# RaspComputeModule_4_IO.net
KiCad netlist of a schematic drawn in Altium Designer
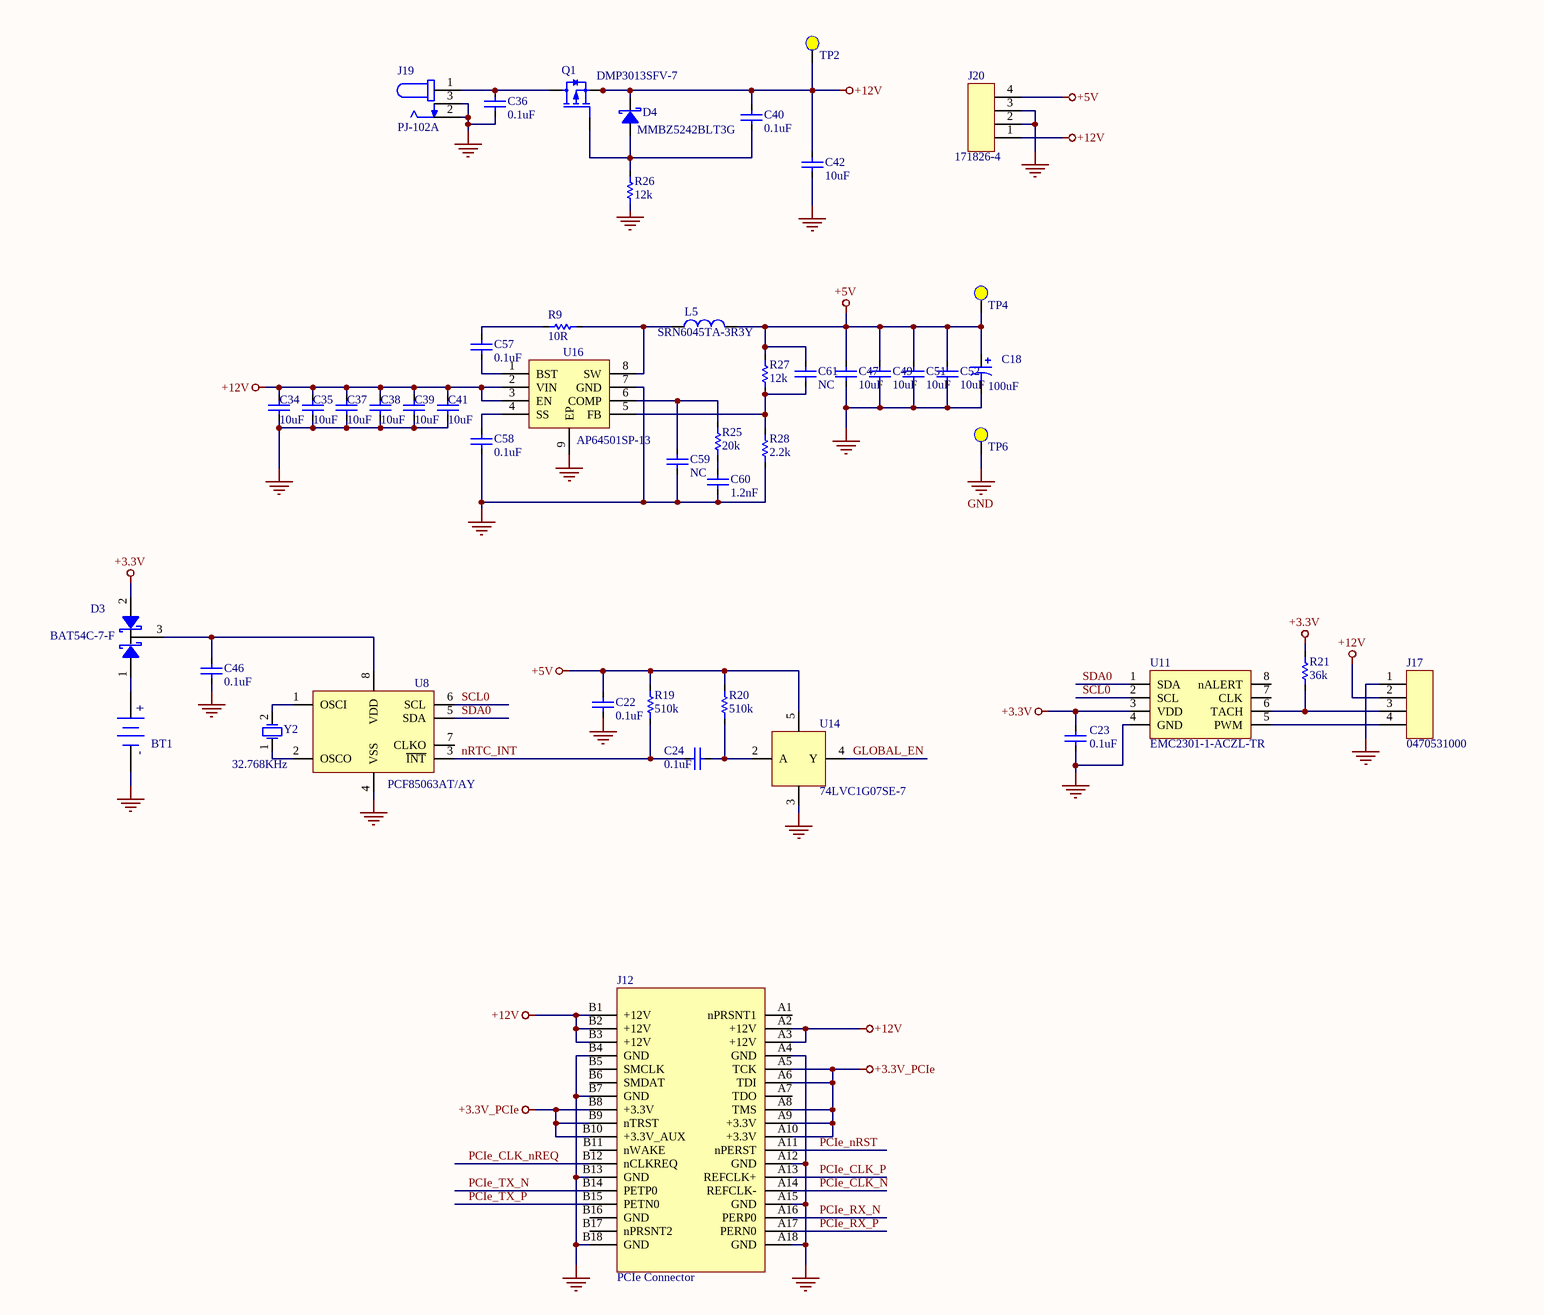
[diagram p0: RaspComputeModule_4_IO.SchDoc, top left]
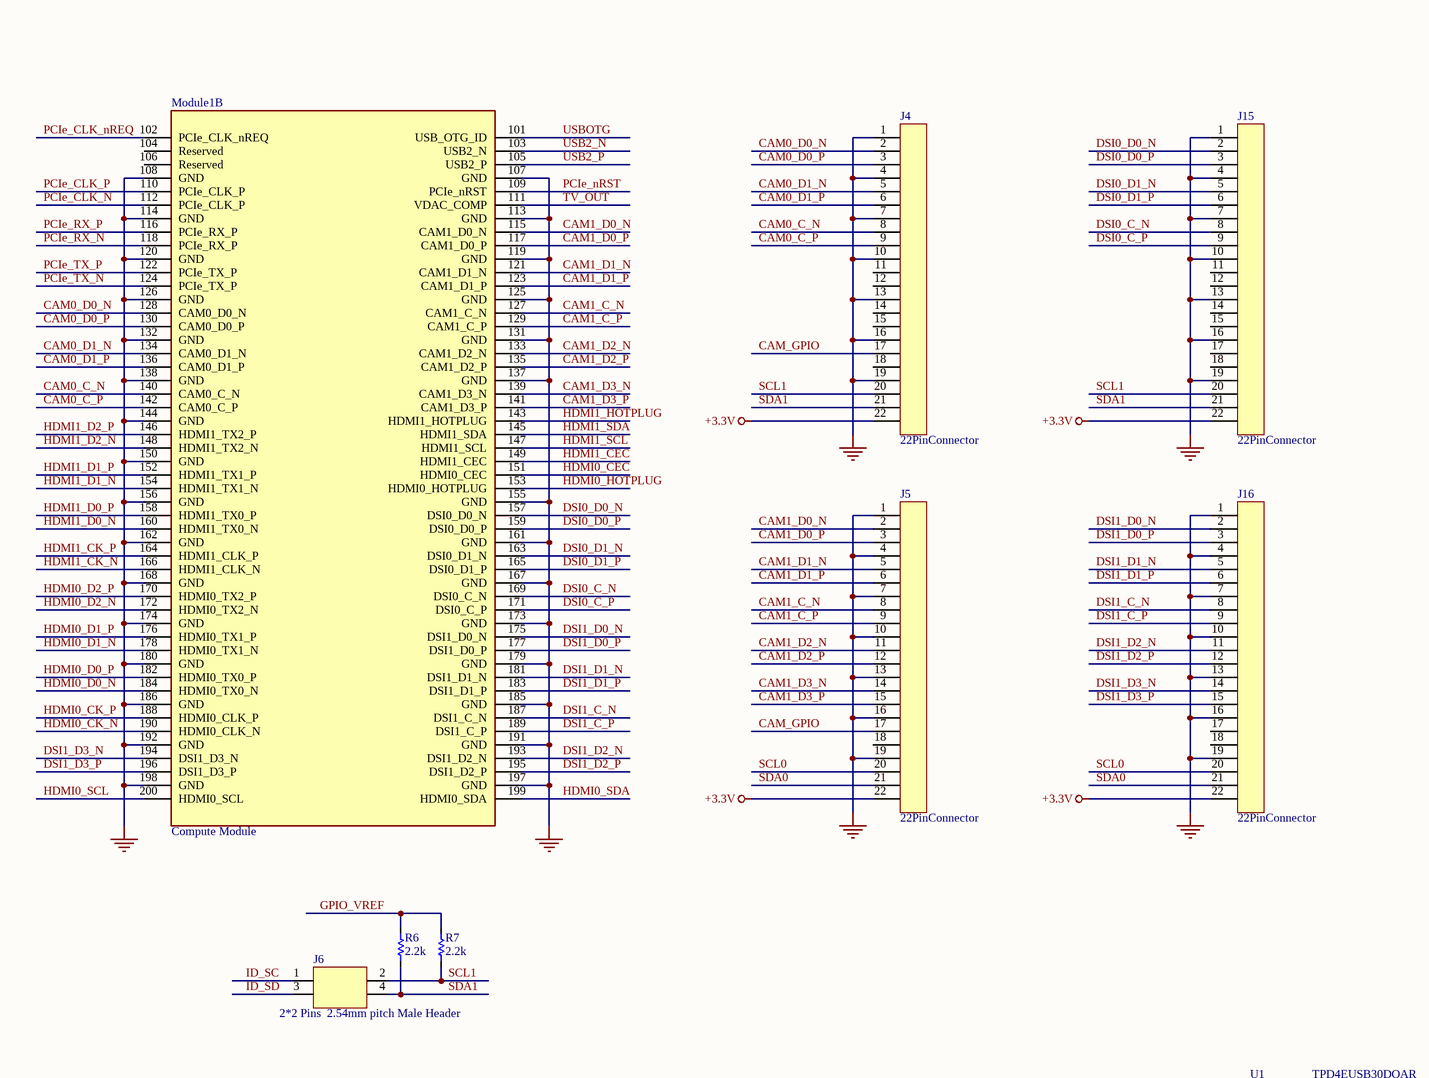
[diagram p1: RaspComputeModule_4_IO.SchDoc, top right]
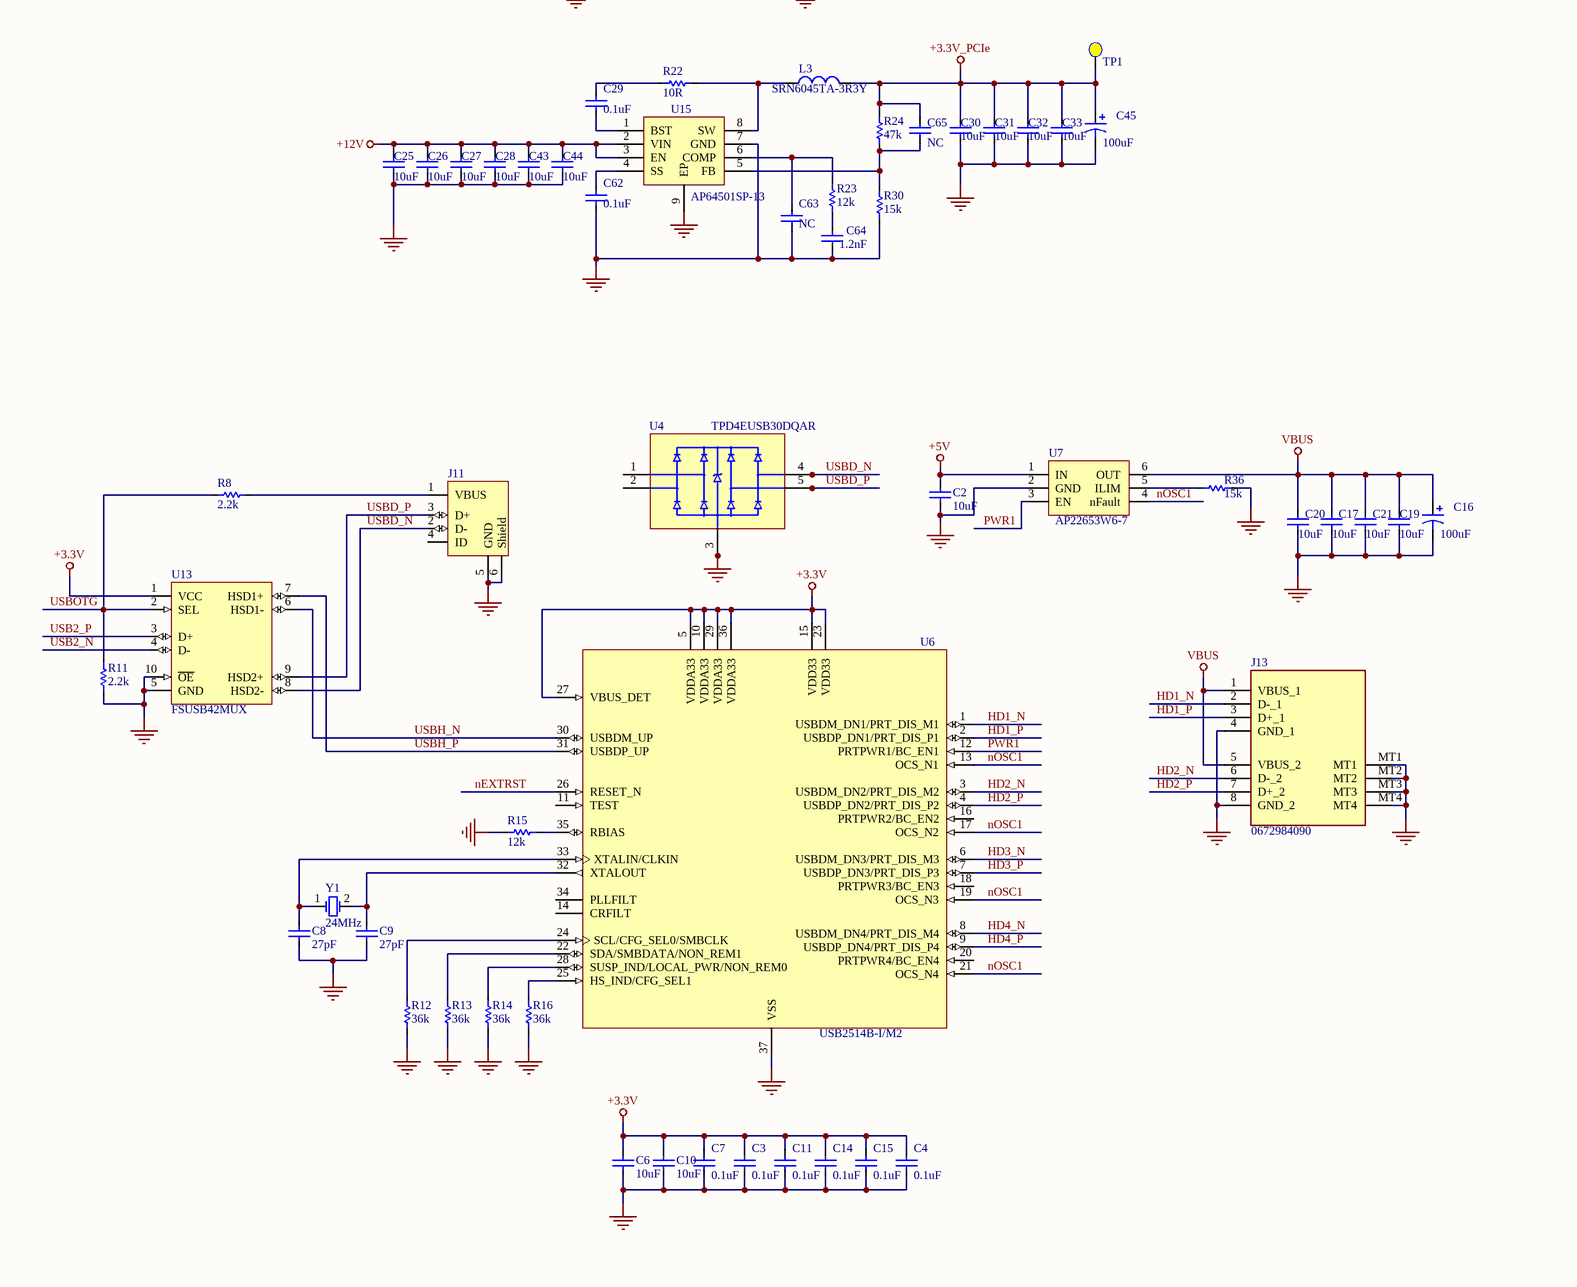
[diagram p2: RaspComputeModule_4_IO.SchDoc, bottom left]
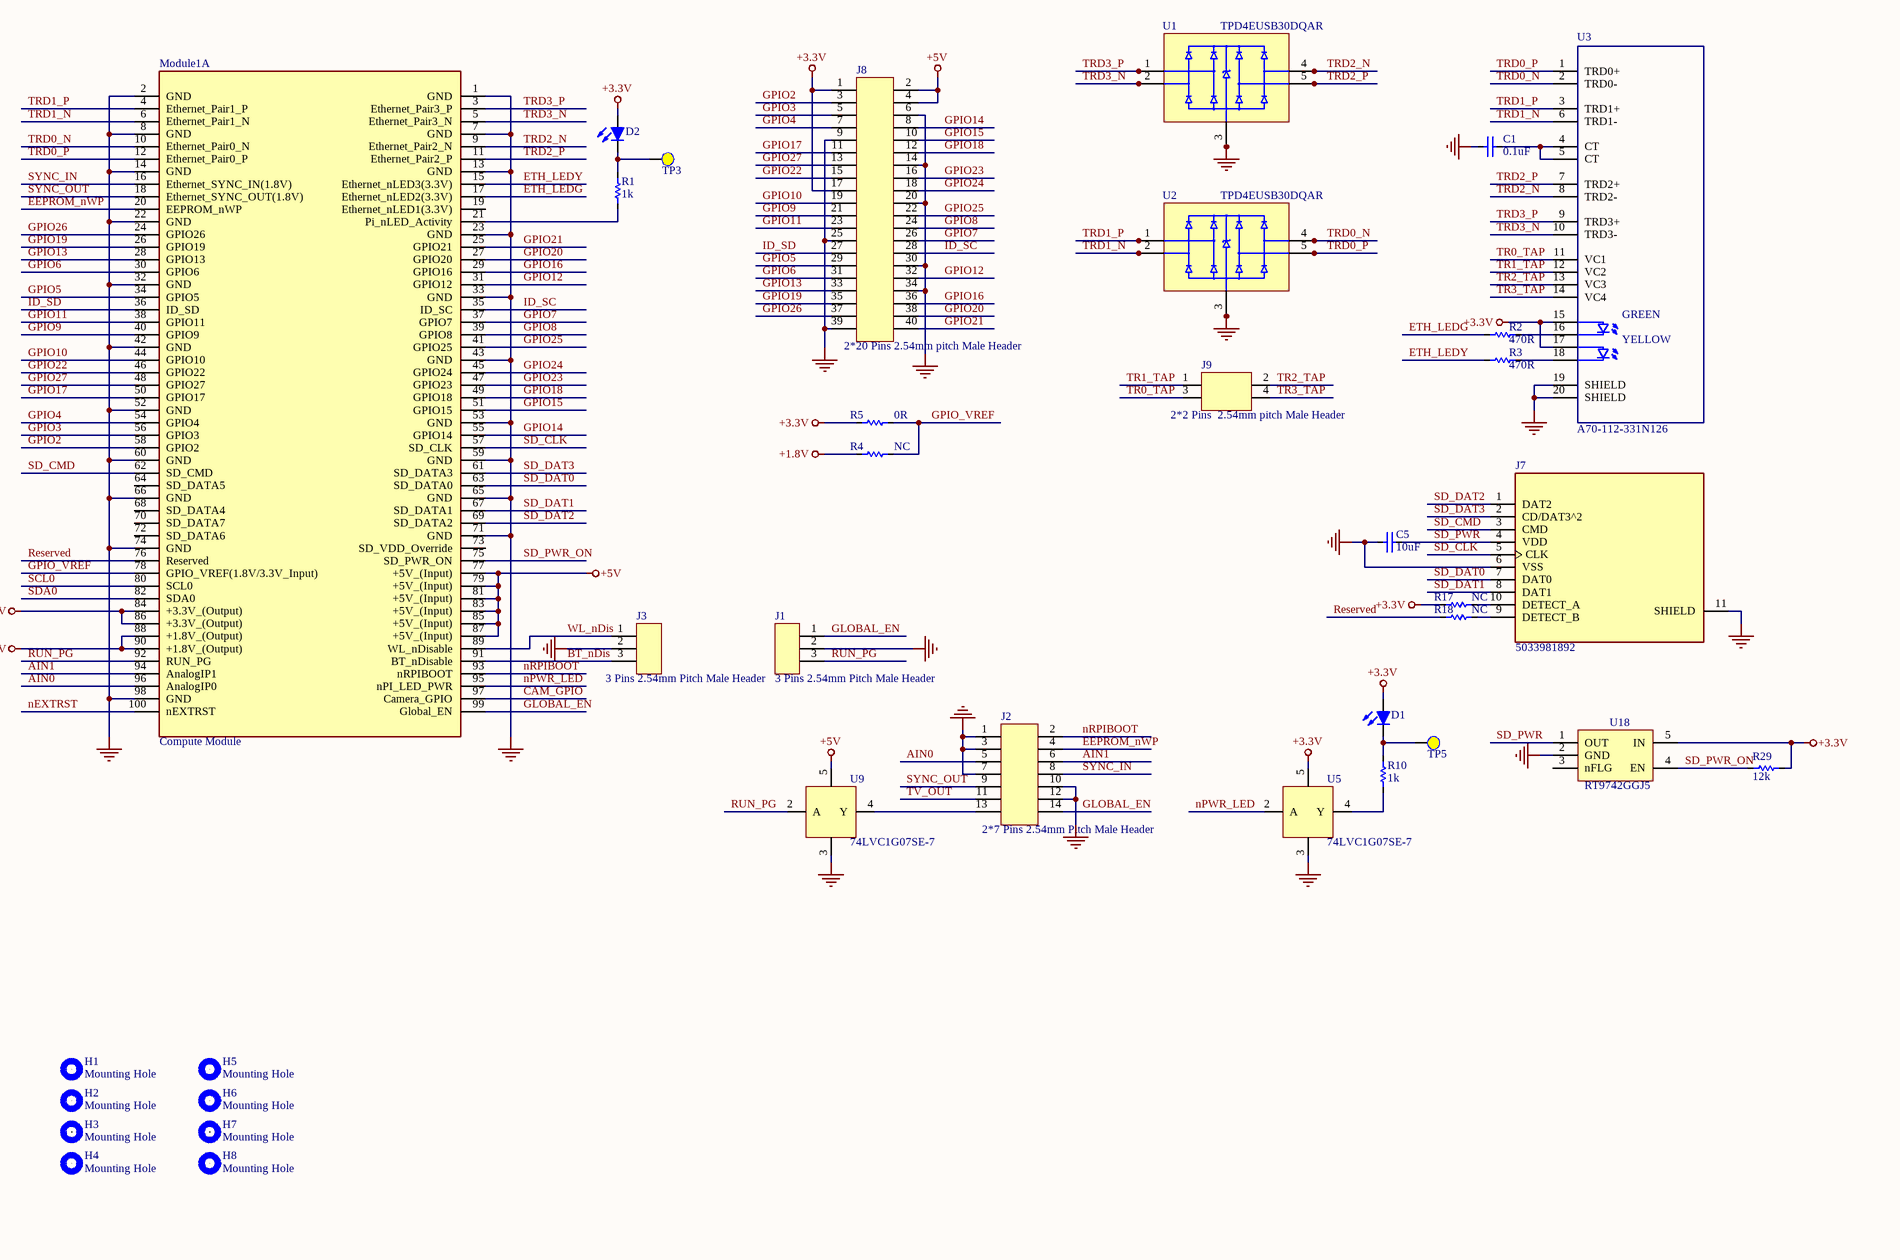
[diagram p3: RaspComputeModule_4_IO.SchDoc, bottom right]

(export (version "E")
  (design (tool "Eeschema 10.0.6"))
  (components
    (comp (ref "BT1")
      (value "3034")
      (footprint "BatteryHolder_Keystone_3034_1x20mm")
      (description "BATTERY RETAINER COIN 20MM SMD")
      (fields (field (name "MANUFACTURER") "Keystone Electronics"))
      (libsource (lib "schematic_library") (part "BATTERY_18650"))
    )
    (comp (ref "C1")
      (value "0.1uF")
      (footprint "C_0402_1005Metric")
      (description "0.1µF ±10% 50V")
      (fields
        (field (name "MANUFACTURER") "Yageo")
        (field (name "MANUFACTURER PART NUMBER") "CC0402KRX5R9BB104")
      )
      (libsource (lib "Miscellaneous Devices") (part "Cap"))
    )
    (comp (ref "C2")
      (value "10uF")
      (footprint "C_0805_2012Metric")
      (description "10µF ±10% 35V")
      (fields
        (field (name "MANUFACTURER") "Murata")
        (field (name "MANUFACTURER PART NUMBER") "GRM21BR6YA106KE43L")
      )
      (libsource (lib "Miscellaneous Devices") (part "Cap"))
    )
    (comp (ref "C3")
      (value "0.1uF")
      (footprint "C_0402_1005Metric")
      (description "0.1µF ±10% 50V")
      (fields
        (field (name "MANUFACTURER") "Yageo")
        (field (name "MANUFACTURER PART NUMBER") "CC0402KRX5R9BB104")
      )
      (libsource (lib "Miscellaneous Devices") (part "Cap"))
    )
    (comp (ref "C4")
      (value "0.1uF")
      (footprint "C_0402_1005Metric")
      (description "0.1µF ±10% 50V")
      (fields
        (field (name "MANUFACTURER") "Yageo")
        (field (name "MANUFACTURER PART NUMBER") "CC0402KRX5R9BB104")
      )
      (libsource (lib "Miscellaneous Devices") (part "Cap"))
    )
    (comp (ref "C5")
      (value "10uF")
      (footprint "C_0805_2012Metric")
      (description "10µF ±10% 35V")
      (fields
        (field (name "MANUFACTURER") "Murata")
        (field (name "MANUFACTURER PART NUMBER") "GRM21BR6YA106KE43L")
      )
      (libsource (lib "Miscellaneous Devices") (part "Cap"))
    )
    (comp (ref "C6")
      (value "10uF")
      (footprint "C_0805_2012Metric")
      (description "10µF ±10% 35V")
      (fields
        (field (name "MANUFACTURER") "Murata")
        (field (name "MANUFACTURER PART NUMBER") "GRM21BR6YA106KE43L")
      )
      (libsource (lib "Miscellaneous Devices") (part "Cap"))
    )
    (comp (ref "C7")
      (value "0.1uF")
      (footprint "C_0402_1005Metric")
      (description "0.1µF ±10% 50V")
      (fields
        (field (name "MANUFACTURER") "Yageo")
        (field (name "MANUFACTURER PART NUMBER") "CC0402KRX5R9BB104")
      )
      (libsource (lib "Miscellaneous Devices") (part "Cap"))
    )
    (comp (ref "C8")
      (value "27pF")
      (footprint "C_0402_1005Metric")
      (description "27pF ±1% 50V")
      (fields
        (field (name "MANUFACTURER") "Yageo")
        (field (name "MANUFACTURER PART NUMBER") "CC0402FRNPO9BN270")
      )
      (libsource (lib "Miscellaneous Devices") (part "Cap"))
    )
    (comp (ref "C9")
      (value "27pF")
      (footprint "C_0402_1005Metric")
      (description "27pF ±1% 50V")
      (fields
        (field (name "MANUFACTURER") "Yageo")
        (field (name "MANUFACTURER PART NUMBER") "CC0402FRNPO9BN270")
      )
      (libsource (lib "Miscellaneous Devices") (part "Cap"))
    )
    (comp (ref "C10")
      (value "10uF")
      (footprint "C_0805_2012Metric")
      (description "10µF ±10% 35V")
      (fields
        (field (name "MANUFACTURER") "Murata")
        (field (name "MANUFACTURER PART NUMBER") "GRM21BR6YA106KE43L")
      )
      (libsource (lib "Miscellaneous Devices") (part "Cap"))
    )
    (comp (ref "C11")
      (value "0.1uF")
      (footprint "C_0402_1005Metric")
      (description "0.1µF ±10% 50V")
      (fields
        (field (name "MANUFACTURER") "Yageo")
        (field (name "MANUFACTURER PART NUMBER") "CC0402KRX5R9BB104")
      )
      (libsource (lib "Miscellaneous Devices") (part "Cap"))
    )
    (comp (ref "C14")
      (value "0.1uF")
      (footprint "C_0402_1005Metric")
      (description "0.1µF ±10% 50V")
      (fields
        (field (name "MANUFACTURER") "Yageo")
        (field (name "MANUFACTURER PART NUMBER") "CC0402KRX5R9BB104")
      )
      (libsource (lib "Miscellaneous Devices") (part "Cap"))
    )
    (comp (ref "C15")
      (value "0.1uF")
      (footprint "C_0402_1005Metric")
      (description "0.1µF ±10% 50V")
      (fields
        (field (name "MANUFACTURER") "Yageo")
        (field (name "MANUFACTURER PART NUMBER") "CC0402KRX5R9BB104")
      )
      (libsource (lib "Miscellaneous Devices") (part "Cap"))
    )
    (comp (ref "C16")
      (value "100uF")
      (footprint "CP_EIA-7343-31_Kemet-D")
      (description "CAP TANT 100UF 20% 10V 2917")
      (fields
        (field (name "MANUFACTURER PART NUMBER") "TAJD107M010RNJ")
        (field (name "MANUFACTURER") "AVX Corporation")
      )
      (libsource (lib "Miscellaneous Devices") (part "Cap Pol1"))
    )
    (comp (ref "C17")
      (value "10uF")
      (footprint "C_0805_2012Metric")
      (description "10µF ±10% 35V")
      (fields
        (field (name "MANUFACTURER") "Murata")
        (field (name "MANUFACTURER PART NUMBER") "GRM21BR6YA106KE43L")
      )
      (libsource (lib "Miscellaneous Devices") (part "Cap"))
    )
    (comp (ref "C18")
      (value "100uF")
      (footprint "CP_EIA-7343-31_Kemet-D")
      (description "CAP TANT 100UF 20% 10V 2917")
      (fields
        (field (name "MANUFACTURER PART NUMBER") "TAJD107M010RNJ")
        (field (name "MANUFACTURER") "AVX Corporation")
      )
      (libsource (lib "Miscellaneous Devices") (part "Cap Pol1"))
    )
    (comp (ref "C19")
      (value "10uF")
      (footprint "C_0805_2012Metric")
      (description "10µF ±10% 35V")
      (fields
        (field (name "MANUFACTURER") "Murata")
        (field (name "MANUFACTURER PART NUMBER") "GRM21BR6YA106KE43L")
      )
      (libsource (lib "Miscellaneous Devices") (part "Cap"))
    )
    (comp (ref "C20")
      (value "10uF")
      (footprint "C_0805_2012Metric")
      (description "10µF ±10% 35V")
      (fields
        (field (name "MANUFACTURER") "Murata")
        (field (name "MANUFACTURER PART NUMBER") "GRM21BR6YA106KE43L")
      )
      (libsource (lib "Miscellaneous Devices") (part "Cap"))
    )
    (comp (ref "C21")
      (value "10uF")
      (footprint "C_0805_2012Metric")
      (description "10µF ±10% 35V")
      (fields
        (field (name "MANUFACTURER") "Murata")
        (field (name "MANUFACTURER PART NUMBER") "GRM21BR6YA106KE43L")
      )
      (libsource (lib "Miscellaneous Devices") (part "Cap"))
    )
    (comp (ref "C22")
      (value "0.1uF")
      (footprint "C_0402_1005Metric")
      (description "0.1µF ±10% 50V")
      (fields
        (field (name "MANUFACTURER") "Yageo")
        (field (name "MANUFACTURER PART NUMBER") "CC0402KRX5R9BB104")
      )
      (libsource (lib "Miscellaneous Devices") (part "Cap"))
    )
    (comp (ref "C23")
      (value "0.1uF")
      (footprint "C_0402_1005Metric")
      (description "0.1µF ±10% 50V")
      (fields
        (field (name "MANUFACTURER") "Yageo")
        (field (name "MANUFACTURER PART NUMBER") "CC0402KRX5R9BB104")
      )
      (libsource (lib "Miscellaneous Devices") (part "Cap"))
    )
    (comp (ref "C24")
      (value "0.1uF")
      (footprint "C_0402_1005Metric")
      (description "0.1µF ±10% 50V")
      (fields
        (field (name "MANUFACTURER") "Yageo")
        (field (name "MANUFACTURER PART NUMBER") "CC0402KRX5R9BB104")
      )
      (libsource (lib "Miscellaneous Devices") (part "Cap"))
    )
    (comp (ref "C25")
      (value "10uF")
      (footprint "C_0805_2012Metric")
      (description "10µF ±10% 35V")
      (fields
        (field (name "MANUFACTURER") "Murata")
        (field (name "MANUFACTURER PART NUMBER") "GRM21BR6YA106KE43L")
      )
      (libsource (lib "Miscellaneous Devices") (part "Cap"))
    )
    (comp (ref "C26")
      (value "10uF")
      (footprint "C_0805_2012Metric")
      (description "10µF ±10% 35V")
      (fields
        (field (name "MANUFACTURER") "Murata")
        (field (name "MANUFACTURER PART NUMBER") "GRM21BR6YA106KE43L")
      )
      (libsource (lib "Miscellaneous Devices") (part "Cap"))
    )
    (comp (ref "C27")
      (value "10uF")
      (footprint "C_0805_2012Metric")
      (description "10µF ±10% 35V")
      (fields
        (field (name "MANUFACTURER") "Murata")
        (field (name "MANUFACTURER PART NUMBER") "GRM21BR6YA106KE43L")
      )
      (libsource (lib "Miscellaneous Devices") (part "Cap"))
    )
    (comp (ref "C28")
      (value "10uF")
      (footprint "C_0805_2012Metric")
      (description "10µF ±10% 35V")
      (fields
        (field (name "MANUFACTURER") "Murata")
        (field (name "MANUFACTURER PART NUMBER") "GRM21BR6YA106KE43L")
      )
      (libsource (lib "Miscellaneous Devices") (part "Cap"))
    )
    (comp (ref "C29")
      (value "0.1uF")
      (footprint "C_0402_1005Metric")
      (description "0.1µF ±10% 50V")
      (fields
        (field (name "MANUFACTURER") "Yageo")
        (field (name "MANUFACTURER PART NUMBER") "CC0402KRX5R9BB104")
      )
      (libsource (lib "Miscellaneous Devices") (part "Cap"))
    )
    (comp (ref "C30")
      (value "10uF")
      (footprint "C_0805_2012Metric")
      (description "10µF ±10% 35V")
      (fields
        (field (name "MANUFACTURER") "Murata")
        (field (name "MANUFACTURER PART NUMBER") "GRM21BR6YA106KE43L")
      )
      (libsource (lib "Miscellaneous Devices") (part "Cap"))
    )
    (comp (ref "C31")
      (value "10uF")
      (footprint "C_0805_2012Metric")
      (description "10µF ±10% 35V")
      (fields
        (field (name "MANUFACTURER") "Murata")
        (field (name "MANUFACTURER PART NUMBER") "GRM21BR6YA106KE43L")
      )
      (libsource (lib "Miscellaneous Devices") (part "Cap"))
    )
    (comp (ref "C32")
      (value "10uF")
      (footprint "C_0805_2012Metric")
      (description "10µF ±10% 35V")
      (fields
        (field (name "MANUFACTURER") "Murata")
        (field (name "MANUFACTURER PART NUMBER") "GRM21BR6YA106KE43L")
      )
      (libsource (lib "Miscellaneous Devices") (part "Cap"))
    )
    (comp (ref "C33")
      (value "10uF")
      (footprint "C_0805_2012Metric")
      (description "10µF ±10% 35V")
      (fields
        (field (name "MANUFACTURER") "Murata")
        (field (name "MANUFACTURER PART NUMBER") "GRM21BR6YA106KE43L")
      )
      (libsource (lib "Miscellaneous Devices") (part "Cap"))
    )
    (comp (ref "C34")
      (value "10uF")
      (footprint "C_0805_2012Metric")
      (description "10µF ±10% 35V")
      (fields
        (field (name "MANUFACTURER") "Murata")
        (field (name "MANUFACTURER PART NUMBER") "GRM21BR6YA106KE43L")
      )
      (libsource (lib "Miscellaneous Devices") (part "Cap"))
    )
    (comp (ref "C35")
      (value "10uF")
      (footprint "C_0805_2012Metric")
      (description "10µF ±10% 35V")
      (fields
        (field (name "MANUFACTURER") "Murata")
        (field (name "MANUFACTURER PART NUMBER") "GRM21BR6YA106KE43L")
      )
      (libsource (lib "Miscellaneous Devices") (part "Cap"))
    )
    (comp (ref "C36")
      (value "0.1uF")
      (footprint "C_0402_1005Metric")
      (description "0.1µF ±10% 50V")
      (fields
        (field (name "MANUFACTURER") "Yageo")
        (field (name "MANUFACTURER PART NUMBER") "CC0402KRX5R9BB104")
      )
      (libsource (lib "Miscellaneous Devices") (part "Cap"))
    )
    (comp (ref "C37")
      (value "10uF")
      (footprint "C_0805_2012Metric")
      (description "10µF ±10% 35V")
      (fields
        (field (name "MANUFACTURER") "Murata")
        (field (name "MANUFACTURER PART NUMBER") "GRM21BR6YA106KE43L")
      )
      (libsource (lib "Miscellaneous Devices") (part "Cap"))
    )
    (comp (ref "C38")
      (value "10uF")
      (footprint "C_0805_2012Metric")
      (description "10µF ±10% 35V")
      (fields
        (field (name "MANUFACTURER") "Murata")
        (field (name "MANUFACTURER PART NUMBER") "GRM21BR6YA106KE43L")
      )
      (libsource (lib "Miscellaneous Devices") (part "Cap"))
    )
    (comp (ref "C39")
      (value "10uF")
      (footprint "C_0805_2012Metric")
      (description "10µF ±10% 35V")
      (fields
        (field (name "MANUFACTURER") "Murata")
        (field (name "MANUFACTURER PART NUMBER") "GRM21BR6YA106KE43L")
      )
      (libsource (lib "Miscellaneous Devices") (part "Cap"))
    )
    (comp (ref "C40")
      (value "0.1uF")
      (footprint "C_0402_1005Metric")
      (description "0.1µF ±10% 50V")
      (fields
        (field (name "MANUFACTURER") "Yageo")
        (field (name "MANUFACTURER PART NUMBER") "CC0402KRX5R9BB104")
      )
      (libsource (lib "Miscellaneous Devices") (part "Cap"))
    )
    (comp (ref "C41")
      (value "10uF")
      (footprint "C_0805_2012Metric")
      (description "10µF ±10% 35V")
      (fields
        (field (name "MANUFACTURER") "Murata")
        (field (name "MANUFACTURER PART NUMBER") "GRM21BR6YA106KE43L")
      )
      (libsource (lib "Miscellaneous Devices") (part "Cap"))
    )
    (comp (ref "C42")
      (value "10uF")
      (footprint "C_0805_2012Metric")
      (description "10µF ±10% 35V")
      (fields
        (field (name "MANUFACTURER") "Murata")
        (field (name "MANUFACTURER PART NUMBER") "GRM21BR6YA106KE43L")
      )
      (libsource (lib "Miscellaneous Devices") (part "Cap"))
    )
    (comp (ref "C43")
      (value "10uF")
      (footprint "C_0805_2012Metric")
      (description "10µF ±10% 35V")
      (fields
        (field (name "MANUFACTURER") "Murata")
        (field (name "MANUFACTURER PART NUMBER") "GRM21BR6YA106KE43L")
      )
      (libsource (lib "Miscellaneous Devices") (part "Cap"))
    )
    (comp (ref "C44")
      (value "10uF")
      (footprint "C_0805_2012Metric")
      (description "10µF ±10% 35V")
      (fields
        (field (name "MANUFACTURER") "Murata")
        (field (name "MANUFACTURER PART NUMBER") "GRM21BR6YA106KE43L")
      )
      (libsource (lib "Miscellaneous Devices") (part "Cap"))
    )
    (comp (ref "C45")
      (value "100uF")
      (footprint "CP_EIA-7343-31_Kemet-D")
      (description "CAP TANT 100UF 20% 10V 2917")
      (fields
        (field (name "MANUFACTURER PART NUMBER") "TAJD107M010RNJ")
        (field (name "MANUFACTURER") "AVX Corporation")
      )
      (libsource (lib "Miscellaneous Devices") (part "Cap Pol1"))
    )
    (comp (ref "C46")
      (value "0.1uF")
      (footprint "C_0402_1005Metric")
      (description "0.1µF ±10% 50V")
      (fields
        (field (name "MANUFACTURER") "Yageo")
        (field (name "MANUFACTURER PART NUMBER") "CC0402KRX5R9BB104")
      )
      (libsource (lib "Miscellaneous Devices") (part "Cap"))
    )
    (comp (ref "C47")
      (value "10uF")
      (footprint "C_0805_2012Metric")
      (description "10µF ±10% 35V")
      (fields
        (field (name "MANUFACTURER") "Murata")
        (field (name "MANUFACTURER PART NUMBER") "GRM21BR6YA106KE43L")
      )
      (libsource (lib "Miscellaneous Devices") (part "Cap"))
    )
    (comp (ref "C49")
      (value "10uF")
      (footprint "C_0805_2012Metric")
      (description "10µF ±10% 35V")
      (fields
        (field (name "MANUFACTURER") "Murata")
        (field (name "MANUFACTURER PART NUMBER") "GRM21BR6YA106KE43L")
      )
      (libsource (lib "Miscellaneous Devices") (part "Cap"))
    )
    (comp (ref "C51")
      (value "10uF")
      (footprint "C_0805_2012Metric")
      (description "10µF ±10% 35V")
      (fields
        (field (name "MANUFACTURER") "Murata")
        (field (name "MANUFACTURER PART NUMBER") "GRM21BR6YA106KE43L")
      )
      (libsource (lib "Miscellaneous Devices") (part "Cap"))
    )
    (comp (ref "C52")
      (value "10uF")
      (footprint "C_0805_2012Metric")
      (description "10µF ±10% 35V")
      (fields
        (field (name "MANUFACTURER") "Murata")
        (field (name "MANUFACTURER PART NUMBER") "GRM21BR6YA106KE43L")
      )
      (libsource (lib "Miscellaneous Devices") (part "Cap"))
    )
    (comp (ref "C57")
      (value "0.1uF")
      (footprint "C_0402_1005Metric")
      (description "0.1µF ±10% 50V")
      (fields
        (field (name "MANUFACTURER") "Yageo")
        (field (name "MANUFACTURER PART NUMBER") "CC0402KRX5R9BB104")
      )
      (libsource (lib "Miscellaneous Devices") (part "Cap"))
    )
    (comp (ref "C58")
      (value "0.1uF")
      (footprint "C_0402_1005Metric")
      (description "0.1µF ±10% 50V")
      (fields
        (field (name "MANUFACTURER") "Yageo")
        (field (name "MANUFACTURER PART NUMBER") "CC0402KRX5R9BB104")
      )
      (libsource (lib "Miscellaneous Devices") (part "Cap"))
    )
    (comp (ref "C59")
      (value "NC")
      (footprint "C_0402_1005Metric")
      (libsource (lib "Miscellaneous Devices") (part "Cap"))
    )
    (comp (ref "C60")
      (value "1.2nF")
      (footprint "C_0402_1005Metric")
      (description "1200pF ±10% 50V")
      (fields
        (field (name "MANUFACTURER") "Murata")
        (field (name "MANUFACTURER PART NUMBER") "GRM155R71H122KA01J")
      )
      (libsource (lib "Miscellaneous Devices") (part "Cap"))
    )
    (comp (ref "C61")
      (value "NC")
      (footprint "C_0402_1005Metric")
      (libsource (lib "Miscellaneous Devices") (part "Cap"))
    )
    (comp (ref "C62")
      (value "0.1uF")
      (footprint "C_0402_1005Metric")
      (description "0.1µF ±10% 50V")
      (fields
        (field (name "MANUFACTURER") "Yageo")
        (field (name "MANUFACTURER PART NUMBER") "CC0402KRX5R9BB104")
      )
      (libsource (lib "Miscellaneous Devices") (part "Cap"))
    )
    (comp (ref "C63")
      (value "NC")
      (footprint "C_0402_1005Metric")
      (libsource (lib "Miscellaneous Devices") (part "Cap"))
    )
    (comp (ref "C64")
      (value "1.2nF")
      (footprint "C_0402_1005Metric")
      (description "1200pF ±10% 50V")
      (fields
        (field (name "MANUFACTURER") "Murata")
        (field (name "MANUFACTURER PART NUMBER") "GRM155R71H122KA01J")
      )
      (libsource (lib "Miscellaneous Devices") (part "Cap"))
    )
    (comp (ref "C65")
      (value "NC")
      (footprint "C_0402_1005Metric")
      (libsource (lib "Miscellaneous Devices") (part "Cap"))
    )
    (comp (ref "D1")
      (value "SML-D12U1WT86")
      (footprint "LED_0603_1608Metric")
      (description "LED RED DIFFUSED 0603 SMD")
      (fields (field (name "MANUFACTURER") "Rohm Semiconductor"))
      (libsource (lib "WirelessCharger") (part "LED1"))
    )
    (comp (ref "D2")
      (value "SML-D12U1WT86")
      (footprint "LED_0603_1608Metric")
      (description "LED RED DIFFUSED 0603 SMD")
      (fields (field (name "MANUFACTURER") "Rohm Semiconductor"))
      (libsource (lib "WirelessCharger") (part "LED1"))
    )
    (comp (ref "D3")
      (value "BAT54C-7-F")
      (footprint "SOT-23")
      (description "DIODE ARRAY SCHOTTKY 30V SOT323")
      (fields
        (field (name "MANUFACTURER") "ON Semiconductor")
        (field (name "MANUFACTURER PART NUMBER") "BAT54CWT1G")
      )
      (libsource (lib "WirelessCharger") (part "BAT54C-7-F"))
    )
    (comp (ref "D4")
      (value "MMBZ5242BLT3G")
      (footprint "D_SOT-23_ANK")
      (description "DIODE ZENER 12V 225MW SOT23-3")
      (fields (field (name "MANUFACTURER") "ON Semiconductor"))
      (libsource (lib "WirelessCharger") (part "Diode 10TQ035"))
    )
    (comp (ref "H1")
      (value "Mounting Hole")
      (footprint "MountingHole_2.7mm_M2.5")
      (libsource (lib "WirelessCharger") (part "Mounting Hole"))
    )
    (comp (ref "H2")
      (value "Mounting Hole")
      (footprint "MountingHole_2.7mm_M2.5")
      (libsource (lib "WirelessCharger") (part "Mounting Hole"))
    )
    (comp (ref "H3")
      (value "Mounting Hole")
      (footprint "MountingHole_2.7mm_M2.5")
      (libsource (lib "WirelessCharger") (part "Mounting Hole"))
    )
    (comp (ref "H4")
      (value "Mounting Hole")
      (footprint "MountingHole_2.7mm_M2.5")
      (libsource (lib "WirelessCharger") (part "Mounting Hole"))
    )
    (comp (ref "H5")
      (value "Mounting Hole")
      (footprint "MountingHole_2.7mm_M2.5")
      (libsource (lib "WirelessCharger") (part "Mounting Hole"))
    )
    (comp (ref "H6")
      (value "Mounting Hole")
      (footprint "MountingHole_2.7mm_M2.5")
      (libsource (lib "WirelessCharger") (part "Mounting Hole"))
    )
    (comp (ref "H7")
      (value "Mounting Hole")
      (footprint "MountingHole_2.7mm_M2.5")
      (libsource (lib "WirelessCharger") (part "Mounting Hole"))
    )
    (comp (ref "H8")
      (value "Mounting Hole")
      (footprint "MountingHole_2.7mm_M2.5")
      (libsource (lib "WirelessCharger") (part "Mounting Hole"))
    )
    (comp (ref "J1")
      (value "3 Pins 2.54mm Pitch Male Header")
      (footprint "PinHeader_1x03_P2.54mm_Vertical")
      (description "3PinConnector")
      (fields (field (name "MANUFACTURER") "Any"))
      (libsource (lib "") (part "3PinConnector_1"))
    )
    (comp (ref "J2")
      (value "2*7 Pins 2.54mm Pitch Male Header")
      (footprint "PinHeader_2x07_P2.54mm_Vertical")
      (fields (field (name "MANUFACTURER") "Any"))
      (libsource (lib "WirelessCharger") (part "14PinConnector"))
    )
    (comp (ref "J3")
      (value "3 Pins 2.54mm Pitch Male Header")
      (footprint "PinHeader_1x03_P2.54mm_Vertical")
      (description "3PinConnector")
      (fields (field (name "MANUFACTURER") "Any"))
      (libsource (lib "WirelessCharger") (part "3PinConnector"))
    )
    (comp (ref "J4")
      (value "22PinConnector")
      (footprint "Hirose_FH12-22S-0.5SH_1x22-1MP_P0.50mm_Horizontal")
      (description "CONN FFC BOTTOM 22POS 0.50MM R/A")
      (fields
        (field (name "MANUFACTURER") "Hirose Electric Co Ltd")
        (field (name "MANUFACTURER PART NUMBER") "FH12-22S-0.5SH(55)")
      )
      (libsource (lib "WirelessCharger") (part "22PinConnector"))
    )
    (comp (ref "J5")
      (value "22PinConnector")
      (footprint "Hirose_FH12-22S-0.5SH_1x22-1MP_P0.50mm_Horizontal")
      (description "CONN FFC BOTTOM 22POS 0.50MM R/A")
      (fields
        (field (name "MANUFACTURER") "Hirose Electric Co Ltd")
        (field (name "MANUFACTURER PART NUMBER") "FH12-22S-0.5SH(55)")
      )
      (libsource (lib "WirelessCharger") (part "22PinConnector"))
    )
    (comp (ref "J6")
      (value "2*2 Pins  2.54mm pitch Male Header")
      (footprint "PinHeader_2x02_P2.54mm_Vertical")
      (description "2*2 Pin Header")
      (fields (field (name "MANUFACTUER PART NUMBER") "Any"))
      (libsource (lib "WirelessCharger") (part "2*2 Pin Header"))
    )
    (comp (ref "J7")
      (value "5033981892")
      (footprint "SDCARD_MOLEX_503398-1892")
      (description "MICRO SD PUSH/PUSH NORMAL 1.28MM 8C")
      (fields (field (name "MANUFACTURER") "Molex"))
      (libsource (lib "WirelessCharger") (part "503398-1892"))
    )
    (comp (ref "J8")
      (value "2*20 Pins 2.54mm pitch Male Header")
      (footprint "PinHeader_2x20_P2.54mm_Vertical")
      (description "40PinConnector")
      (fields (field (name "MANUFACTURER") "Any"))
      (libsource (lib "WirelessCharger") (part "40PinConnector"))
    )
    (comp (ref "J9")
      (value "2*2 Pins  2.54mm pitch Male Header")
      (footprint "PinHeader_2x02_P2.54mm_Vertical")
      (description "2*2 Pin Header")
      (fields (field (name "MANUFACTUER PART NUMBER") "Any"))
      (libsource (lib "WirelessCharger") (part "2*2 Pin Header"))
    )
    (comp (ref "J11")
      (value "10118194-0001LF")
      (footprint "10118194-0001LF")
      (description "CONN RCPT USB2.0 MICRO B SMD R/A")
      (fields (field (name "MANUFACTURER") "Amphenol FCI"))
      (libsource (lib "WirelessCharger") (part "10118194-0001LF"))
    )
    (comp (ref "J12")
      (value "PCIe Connector")
      (footprint "PCIex1-36")
      (fields
        (field (name "MANUFACTURER") "Samtec")
        (field (name "MANUFACTURER PART NUMBER") "PCIE-036-02-S-D-RA")
      )
      (libsource (lib "WirelessCharger") (part "PCIe Connector"))
    )
    (comp (ref "J13")
      (value "0672984090")
      (footprint "MOLEX_USB_67298-4090")
      (description "CONN RCPT TYPEA STACKED 8POS R/A")
      (fields (field (name "MANUFACTURER") "Molex"))
      (libsource (lib "WirelessCharger") (part "Double USB Connector"))
    )
    (comp (ref "J15")
      (value "22PinConnector")
      (footprint "Hirose_FH12-22S-0.5SH_1x22-1MP_P0.50mm_Horizontal")
      (description "CONN FFC BOTTOM 22POS 0.50MM R/A")
      (fields
        (field (name "MANUFACTURER") "Hirose Electric Co Ltd")
        (field (name "MANUFACTURER PART NUMBER") "FH12-22S-0.5SH(55)")
      )
      (libsource (lib "WirelessCharger") (part "22PinConnector"))
    )
    (comp (ref "J16")
      (value "22PinConnector")
      (footprint "Hirose_FH12-22S-0.5SH_1x22-1MP_P0.50mm_Horizontal")
      (description "CONN FFC BOTTOM 22POS 0.50MM R/A")
      (fields
        (field (name "MANUFACTURER") "Hirose Electric Co Ltd")
        (field (name "MANUFACTURER PART NUMBER") "FH12-22S-0.5SH(55)")
      )
      (libsource (lib "WirelessCharger") (part "22PinConnector"))
    )
    (comp (ref "J17")
      (value "0470531000")
      (footprint "FanPinHeader_1x04_P2.54mm_Vertical")
      (description "4PinConnector")
      (fields (field (name "MANUFACTURER") "Molex"))
      (libsource (lib "WirelessCharger") (part "4PinConnector"))
    )
    (comp (ref "J19")
      (value "PJ-102A")
      (footprint "CUI_PJ-102A")
      (description "CONN PWR JACK 2X5.5MM SOLDER")
      (fields (field (name "MANUFACTURER") "CUI Devices"))
      (libsource (lib "WirelessCharger") (part "PJ-102A"))
    )
    (comp (ref "J20")
      (value "171826-4")
      (footprint "TE_171826-4")
      (description "CONN HEADER R/A 4POS 2.5MM")
      (fields (field (name "MANUFACTURER") "TE Connectivity AMP Connectors"))
      (libsource (lib "") (part "4PinConnector_1"))
    )
    (comp (ref "L3")
      (value "SRN6045TA-3R3Y")
      (footprint "L_Bourns_SRN6045TA")
      (description "FIXED IND 3.3UH 5A 21 MOHM SMD")
      (fields (field (name "MANUFACTURER") "Bourns Inc."))
      (libsource (lib "WirelessCharger") (part "Inductor"))
    )
    (comp (ref "L5")
      (value "SRN6045TA-3R3Y")
      (footprint "L_Bourns_SRN6045TA")
      (description "FIXED IND 3.3UH 5A 21 MOHM SMD")
      (fields (field (name "MANUFACTURER") "Bourns Inc."))
      (libsource (lib "WirelessCharger") (part "Inductor"))
    )
    (comp (ref "Module1")
      (value "Compute Module")
      (footprint "Raspberry-Pi-4-Compute-Module")
      (description "CONN RCPT 100POS SMD GOLD")
      (fields
        (field (name "MANUFACTURER") "Hirose Electric Co Ltd")
        (field (name "MANUFACTURER PART NUMBER") "DF40C-100DS-0.4V(51)")
      )
      (libsource (lib "") (part "ComputeModule4_1"))
    )
    (comp (ref "Q1")
      (value "DMP3013SFV-7")
      (footprint "Diodes_PowerDI3333-8")
      (fields (field (name "MANUFACTURER") "Diodes Incorporated"))
      (libsource (lib "WirelessCharger") (part "DMP3013SFV-7"))
    )
    (comp (ref "R1")
      (value "1k")
      (footprint "R_0402_1005Metric")
      (description "1 kOhms ±1% 0.063W")
      (fields
        (field (name "MANUFACTURER") "Yageo")
        (field (name "MANUFACTURER PART NUMBER") "RC0402FR-071KL")
      )
      (libsource (lib "Miscellaneous Devices") (part "Res Semi"))
    )
    (comp (ref "R2")
      (value "470R")
      (footprint "R_0402_1005Metric")
      (description "470 Ohms ±1% 0.063W")
      (fields
        (field (name "MANUFACTURER") "Yageo")
        (field (name "MANUFACTURER PART NUMBER") "RC0402FR-07470RL")
      )
      (libsource (lib "Miscellaneous Devices") (part "Res Semi"))
    )
    (comp (ref "R3")
      (value "470R")
      (footprint "R_0402_1005Metric")
      (description "470 Ohms ±1% 0.063W")
      (fields
        (field (name "MANUFACTURER") "Yageo")
        (field (name "MANUFACTURER PART NUMBER") "RC0402FR-07470RL")
      )
      (libsource (lib "Miscellaneous Devices") (part "Res Semi"))
    )
    (comp (ref "R4")
      (value "NC")
      (footprint "R_0402_1005Metric")
      (libsource (lib "Miscellaneous Devices") (part "Res Semi"))
    )
    (comp (ref "R5")
      (value "0R")
      (footprint "R_0402_1005Metric")
      (description "0 Ohms Jumper 0.063W")
      (fields
        (field (name "MANUFACTURER") "Yageo")
        (field (name "MANUFACTURER PART NUMBER") "RC0402FR-070RL")
      )
      (libsource (lib "Miscellaneous Devices") (part "Res Semi"))
    )
    (comp (ref "R6")
      (value "2.2k")
      (footprint "R_0402_1005Metric")
      (description "2.2 kOhms ±1% 0.063W")
      (fields
        (field (name "MANUFACTURER") "Yageo")
        (field (name "MANUFACTURER PART NUMBER") "RC0402FR-072K2L")
      )
      (libsource (lib "Miscellaneous Devices") (part "Res Semi"))
    )
    (comp (ref "R7")
      (value "2.2k")
      (footprint "R_0402_1005Metric")
      (description "2.2 kOhms ±1% 0.063W")
      (fields
        (field (name "MANUFACTURER") "Yageo")
        (field (name "MANUFACTURER PART NUMBER") "RC0402FR-072K2L")
      )
      (libsource (lib "Miscellaneous Devices") (part "Res Semi"))
    )
    (comp (ref "R8")
      (value "2.2k")
      (footprint "R_0402_1005Metric")
      (description "2.2 kOhms ±1% 0.063W")
      (fields
        (field (name "MANUFACTURER") "Yageo")
        (field (name "MANUFACTURER PART NUMBER") "RC0402FR-072K2L")
      )
      (libsource (lib "Miscellaneous Devices") (part "Res Semi"))
    )
    (comp (ref "R9")
      (value "10R")
      (footprint "R_0402_1005Metric")
      (description "10 Ohms ±1% 0.063W")
      (fields
        (field (name "MANUFACTURER") "Yageo")
        (field (name "MANUFACTURER PART NUMBER") "RC0402FR-0710RL")
      )
      (libsource (lib "Miscellaneous Devices") (part "Res Semi"))
    )
    (comp (ref "R10")
      (value "1k")
      (footprint "R_0402_1005Metric")
      (description "1 kOhms ±1% 0.063W")
      (fields
        (field (name "MANUFACTURER") "Yageo")
        (field (name "MANUFACTURER PART NUMBER") "RC0402FR-071KL")
      )
      (libsource (lib "Miscellaneous Devices") (part "Res Semi"))
    )
    (comp (ref "R11")
      (value "2.2k")
      (footprint "R_0402_1005Metric")
      (description "2.2 kOhms ±1% 0.063W")
      (fields
        (field (name "MANUFACTURER") "Yageo")
        (field (name "MANUFACTURER PART NUMBER") "RC0402FR-072K2L")
      )
      (libsource (lib "Miscellaneous Devices") (part "Res Semi"))
    )
    (comp (ref "R12")
      (value "36k")
      (footprint "R_0402_1005Metric")
      (description "36 kOhms ±1% 0.063W")
      (fields
        (field (name "MANUFACTURER") "Yageo")
        (field (name "MANUFACTURER PART NUMBER") "RC0402FR-0736KL")
      )
      (libsource (lib "Miscellaneous Devices") (part "Res Semi"))
    )
    (comp (ref "R13")
      (value "36k")
      (footprint "R_0402_1005Metric")
      (description "36 kOhms ±1% 0.063W")
      (fields
        (field (name "MANUFACTURER") "Yageo")
        (field (name "MANUFACTURER PART NUMBER") "RC0402FR-0736KL")
      )
      (libsource (lib "Miscellaneous Devices") (part "Res Semi"))
    )
    (comp (ref "R14")
      (value "36k")
      (footprint "R_0402_1005Metric")
      (description "36 kOhms ±1% 0.063W")
      (fields
        (field (name "MANUFACTURER") "Yageo")
        (field (name "MANUFACTURER PART NUMBER") "RC0402FR-0736KL")
      )
      (libsource (lib "Miscellaneous Devices") (part "Res Semi"))
    )
    (comp (ref "R15")
      (value "12k")
      (footprint "R_0402_1005Metric")
      (description "12 kOhms ±1% 0.063W")
      (fields
        (field (name "MANUFACTURER") "Yageo")
        (field (name "MANUFACTURER PART NUMBER") "RC0402FR-0712KL")
      )
      (libsource (lib "Miscellaneous Devices") (part "Res Semi"))
    )
    (comp (ref "R16")
      (value "36k")
      (footprint "R_0402_1005Metric")
      (description "36 kOhms ±1% 0.063W")
      (fields
        (field (name "MANUFACTURER") "Yageo")
        (field (name "MANUFACTURER PART NUMBER") "RC0402FR-0736KL")
      )
      (libsource (lib "Miscellaneous Devices") (part "Res Semi"))
    )
    (comp (ref "R17")
      (value "NC")
      (footprint "R_0402_1005Metric")
      (libsource (lib "Miscellaneous Devices") (part "Res Semi"))
    )
    (comp (ref "R18")
      (value "NC")
      (footprint "R_0402_1005Metric")
      (libsource (lib "Miscellaneous Devices") (part "Res Semi"))
    )
    (comp (ref "R19")
      (value "510k")
      (footprint "R_0402_1005Metric")
      (description "510 kOhms ±1% 0.063W")
      (fields
        (field (name "MANUFACTURER") "Yageo")
        (field (name "MANUFACTURER PART NUMBER") "RC0402FR-07510KL")
      )
      (libsource (lib "Miscellaneous Devices") (part "Res Semi"))
    )
    (comp (ref "R20")
      (value "510k")
      (footprint "R_0402_1005Metric")
      (description "510 kOhms ±1% 0.063W")
      (fields
        (field (name "MANUFACTURER") "Yageo")
        (field (name "MANUFACTURER PART NUMBER") "RC0402FR-07510KL")
      )
      (libsource (lib "Miscellaneous Devices") (part "Res Semi"))
    )
    (comp (ref "R21")
      (value "36k")
      (footprint "R_0402_1005Metric")
      (description "36 kOhms ±1% 0.063W")
      (fields
        (field (name "MANUFACTURER") "Yageo")
        (field (name "MANUFACTURER PART NUMBER") "RC0402FR-0736KL")
      )
      (libsource (lib "Miscellaneous Devices") (part "Res Semi"))
    )
    (comp (ref "R22")
      (value "10R")
      (footprint "R_0402_1005Metric")
      (description "10 Ohms ±1% 0.063W")
      (fields
        (field (name "MANUFACTURER") "Yageo")
        (field (name "MANUFACTURER PART NUMBER") "RC0402FR-0710RL")
      )
      (libsource (lib "Miscellaneous Devices") (part "Res Semi"))
    )
    (comp (ref "R23")
      (value "12k")
      (footprint "R_0402_1005Metric")
      (description "12 kOhms ±1% 0.063W")
      (fields
        (field (name "MANUFACTURER") "Yageo")
        (field (name "MANUFACTURER PART NUMBER") "RC0402FR-0712KL")
      )
      (libsource (lib "Miscellaneous Devices") (part "Res Semi"))
    )
    (comp (ref "R24")
      (value "47k")
      (footprint "R_0402_1005Metric")
      (description "47 kOhms ±1% 0.063W")
      (fields
        (field (name "MANUFACTURER") "Yageo")
        (field (name "MANUFACTURER PART NUMBER") "RC0402FR-0747KL")
      )
      (libsource (lib "Miscellaneous Devices") (part "Res Semi"))
    )
    (comp (ref "R25")
      (value "20k")
      (footprint "R_0402_1005Metric")
      (description "20 kOhms ±1% 0.063W")
      (fields
        (field (name "MANUFACTURER") "Yageo")
        (field (name "MANUFACTURER PART NUMBER") "RC0402FR-0720KL")
      )
      (libsource (lib "Miscellaneous Devices") (part "Res Semi"))
    )
    (comp (ref "R26")
      (value "12k")
      (footprint "R_0402_1005Metric")
      (description "12 kOhms ±1% 0.063W")
      (fields
        (field (name "MANUFACTURER") "Yageo")
        (field (name "MANUFACTURER PART NUMBER") "RC0402FR-0712KL")
      )
      (libsource (lib "Miscellaneous Devices") (part "Res Semi"))
    )
    (comp (ref "R27")
      (value "12k")
      (footprint "R_0402_1005Metric")
      (description "12 kOhms ±1% 0.063W")
      (fields
        (field (name "MANUFACTURER") "Yageo")
        (field (name "MANUFACTURER PART NUMBER") "RC0402FR-0712KL")
      )
      (libsource (lib "Miscellaneous Devices") (part "Res Semi"))
    )
    (comp (ref "R28")
      (value "2.2k")
      (footprint "R_0402_1005Metric")
      (description "2.2 kOhms ±1% 0.063W")
      (fields
        (field (name "MANUFACTURER") "Yageo")
        (field (name "MANUFACTURER PART NUMBER") "RC0402FR-072K2L")
      )
      (libsource (lib "Miscellaneous Devices") (part "Res Semi"))
    )
    (comp (ref "R29")
      (value "12k")
      (footprint "R_0402_1005Metric")
      (description "12 kOhms ±1% 0.063W")
      (fields
        (field (name "MANUFACTURER") "Yageo")
        (field (name "MANUFACTURER PART NUMBER") "RC0402FR-0712KL")
      )
      (libsource (lib "Miscellaneous Devices") (part "Res Semi"))
    )
    (comp (ref "R30")
      (value "15k")
      (footprint "R_0402_1005Metric")
      (description "15 kOhms ±1% 0.063W")
      (fields
        (field (name "MANUFACTURER") "Yageo")
        (field (name "MANUFACTURER PART NUMBER") "RC0402FR-0715KL")
      )
      (libsource (lib "Miscellaneous Devices") (part "Res Semi"))
    )
    (comp (ref "R36")
      (value "15k")
      (footprint "R_0402_1005Metric")
      (description "15 kOhms ±1% 0.063W")
      (fields
        (field (name "MANUFACTURER") "Yageo")
        (field (name "MANUFACTURER PART NUMBER") "RC0402FR-0715KL")
      )
      (libsource (lib "Miscellaneous Devices") (part "Res Semi"))
    )
    (comp (ref "TP1")
      (value "testpoint")
      (footprint "TestPoint_Pad_2.0x2.0mm")
      (libsource (lib "WirelessCharger") (part "testpoint"))
    )
    (comp (ref "TP2")
      (value "testpoint")
      (footprint "TestPoint_Pad_2.0x2.0mm")
      (libsource (lib "WirelessCharger") (part "testpoint"))
    )
    (comp (ref "TP3")
      (value "testpoint")
      (footprint "TestPoint_Pad_2.0x2.0mm")
      (libsource (lib "WirelessCharger") (part "testpoint"))
    )
    (comp (ref "TP4")
      (value "testpoint")
      (footprint "TestPoint_Pad_2.0x2.0mm")
      (libsource (lib "WirelessCharger") (part "testpoint"))
    )
    (comp (ref "TP5")
      (value "testpoint")
      (footprint "TestPoint_Pad_2.0x2.0mm")
      (libsource (lib "WirelessCharger") (part "testpoint"))
    )
    (comp (ref "TP6")
      (value "testpoint")
      (footprint "TestPoint_Pad_2.0x2.0mm")
      (libsource (lib "WirelessCharger") (part "testpoint"))
    )
    (comp (ref "U1")
      (value "TPD4EUSB30DQAR")
      (footprint "USON-10_2.5x1.0mm_P0.5mm")
      (description "TVS DIODE 5.5V 8V 10USON")
      (fields (field (name "MF") "Texas Instruments"))
      (libsource (lib "WirelessCharger") (part "TPD4EUSB30DQAR"))
    )
    (comp (ref "U2")
      (value "TPD4EUSB30DQAR")
      (footprint "USON-10_2.5x1.0mm_P0.5mm")
      (description "TVS DIODE 5.5V 8V 10USON")
      (fields (field (name "MF") "Texas Instruments"))
      (libsource (lib "WirelessCharger") (part "TPD4EUSB30DQAR"))
    )
    (comp (ref "U3")
      (value "A70-112-331N126")
      (footprint "TRJG0926HENL")
      (description "RJ45 MAGNETIC JACK WITH LED")
      (fields (field (name "MANUFACTURER") "LINK-PP"))
      (libsource (lib "A70-112-331N126") (part "A70-112-331N126"))
    )
    (comp (ref "U4")
      (value "TPD4EUSB30DQAR")
      (footprint "USON-10_2.5x1.0mm_P0.5mm")
      (description "TVS DIODE 5.5V 8V 10USON")
      (fields (field (name "MF") "Texas Instruments"))
      (libsource (lib "WirelessCharger") (part "TPD4EUSB30DQAR"))
    )
    (comp (ref "U5")
      (value "74LVC1G07SE-7")
      (footprint "SOT-353_SC-70-5")
      (description "IC BUF NON-INVERT 5.5V SOT353")
      (fields (field (name "MANUFACTURER") "Nexperia"))
      (libsource (lib "WirelessCharger") (part "74LVC1G07SE-7"))
    )
    (comp (ref "U6")
      (value "USB2514B-I/M2")
      (footprint "QFN-36-1EP_6x6mm_P0.5mm_EP3.7x3.7mm")
      (description "USB Hub Controller USB Interface 36-SQFN _6x6_")
      (fields (field (name "MANUFACTURER") "Microchip"))
      (libsource (lib "WirelessCharger") (part "USB2514B-I/M2"))
    )
    (comp (ref "U7")
      (value "AP22653W6-7")
      (footprint "SOT-23-6")
      (description "LOAD SWITCH,SOT26,T&R,3K")
      (fields (field (name "MANUFACTURER") "Diodes Incorporated"))
      (libsource (lib "WirelessCharger") (part "AP22653W6-7"))
    )
    (comp (ref "U8")
      (value "PCF85063AT/AY")
      (footprint "SOIC-8_3.9x4.9mm_P1.27mm")
      (description "IC RTC CLK/CALENDAR I2C 8SOIC")
      (fields (field (name "MANUFACTURER") "NXP USA Inc."))
      (libsource (lib "WirelessCharger") (part "PCF85063AT/AAZ"))
    )
    (comp (ref "U9")
      (value "74LVC1G07SE-7")
      (footprint "SOT-353_SC-70-5")
      (description "IC BUF NON-INVERT 5.5V SOT353")
      (fields (field (name "MANUFACTURER") "Nexperia"))
      (libsource (lib "WirelessCharger") (part "74LVC1G07SE-7"))
    )
    (comp (ref "U11")
      (value "EMC2301-1-ACZL-TR")
      (footprint "MSOP-8_3x3mm_P0.65mm")
      (description "IC MOTOR DRIVER 3V-3.6V 8MSOP")
      (fields (field (name "MANUFACTURER") "Microchip Technology"))
      (libsource (lib "WirelessCharger") (part "EMC2301-1-ACZL-TR"))
    )
    (comp (ref "U13")
      (value "FSUSB42MUX")
      (footprint "MSOP-10_3x3mm_P0.5mm")
      (description "USB Switch IC 1 Channel 10-MSOP")
      (fields (field (name "MANUFACTURER") "ON Semiconductor"))
      (libsource (lib "WirelessCharger") (part "FSUSB42MUX"))
    )
    (comp (ref "U14")
      (value "74LVC1G07SE-7")
      (footprint "SOT-353_SC-70-5")
      (description "IC BUF NON-INVERT 5.5V SOT353")
      (fields (field (name "MANUFACTURER") "Nexperia"))
      (libsource (lib "WirelessCharger") (part "74LVC1G07SE-7"))
    )
    (comp (ref "U15")
      (value "AP64501SP-13")
      (footprint "SOIC-8-1EP_3.9x4.9mm_P1.27mm_EP2.95x4.9mm_Mask2.71x3.4mm_ThermalVias")
      (description "DCDC CONV HV BUCK SO-8EP")
      (fields (field (name "MANUFACTURER") "Diodes Incorporated"))
      (libsource (lib "WirelessCharger") (part "AP64501SP-13"))
    )
    (comp (ref "U16")
      (value "AP64501SP-13")
      (footprint "SOIC-8-1EP_3.9x4.9mm_P1.27mm_EP2.95x4.9mm_Mask2.71x3.4mm_ThermalVias")
      (description "DCDC CONV HV BUCK SO-8EP")
      (fields (field (name "MANUFACTURER") "Diodes Incorporated"))
      (libsource (lib "WirelessCharger") (part "AP64501SP-13"))
    )
    (comp (ref "U18")
      (value "RT9742GGJ5")
      (footprint "SOT-23-5")
      (description "IC PWR SWTCH N-CHAN 1:1 TSOT23-5")
      (fields (field (name "MANUFACTURER") "Richtek USA Inc."))
      (libsource (lib "WirelessCharger") (part "RT9742GGJ5"))
    )
    (comp (ref "Y1")
      (value "24MHz")
      (footprint "Crystal_SMD_HC49-SD")
      (description "CRYSTAL 24.0000MHZ 20PF SMD")
      (fields
        (field (name "MANUFACTURER") "ECS Inc.")
        (field (name "MANUFACTURER PART NUMBER") "ECS-240-20-5PX-TR")
      )
      (libsource (lib "altium-import") (part "root_0__WirelessCharger.SCHLIB"))
    )
    (comp (ref "Y2")
      (value "32.768KHz")
      (footprint "Crystal_SMD_3215-2Pin_3.2x1.5mm")
      (description "CRYSTAL 32.7680KHZ 12.5PF SMD")
      (fields
        (field (name "MANUFACTURER") "NDK America, Inc.")
        (field (name "MANUFACTURER PART NUMBER") "NX3215SA-32.768K-STD-MUA-8")
      )
      (libsource (lib "altium-import") (part "root_1__WirelessCharger.SCHLIB"))
    )
  )
  (nets
    (net (code "1") (name "+1.8V") (class "Default")
      (node (ref "Module1") (pin "88") (pinfunction "+1.8V_(Output)_88") (pintype "power_in"))
      (node (ref "Module1") (pin "90") (pinfunction "+1.8V_(Output)_90") (pintype "power_in"))
      (node (ref "R4") (pin "1") (pinfunction "1_1") (pintype "passive"))
    )
    (net (code "2") (name "+3.3V") (class "Default")
      (node (ref "C10") (pin "1") (pinfunction "1_1") (pintype "passive"))
      (node (ref "C11") (pin "1") (pinfunction "1_1") (pintype "passive"))
      (node (ref "C14") (pin "1") (pinfunction "1_1") (pintype "passive"))
      (node (ref "C15") (pin "1") (pinfunction "1_1") (pintype "passive"))
      (node (ref "C23") (pin "1") (pinfunction "1_1") (pintype "passive"))
      (node (ref "C3") (pin "1") (pinfunction "1_1") (pintype "passive"))
      (node (ref "C4") (pin "1") (pinfunction "1_1") (pintype "passive"))
      (node (ref "C6") (pin "1") (pinfunction "1_1") (pintype "passive"))
      (node (ref "C7") (pin "1") (pinfunction "1_1") (pintype "passive"))
      (node (ref "D1") (pin "2") (pinfunction "A_2") (pintype "passive"))
      (node (ref "D2") (pin "2") (pinfunction "A_2") (pintype "passive"))
      (node (ref "D3") (pin "2") (pinfunction "2_2") (pintype "passive"))
      (node (ref "J15") (pin "22") (pinfunction "22_22") (pintype "passive"))
      (node (ref "J16") (pin "22") (pinfunction "22_22") (pintype "passive"))
      (node (ref "J4") (pin "22") (pinfunction "22_22") (pintype "passive"))
      (node (ref "J5") (pin "22") (pinfunction "22_22") (pintype "passive"))
      (node (ref "J8") (pin "1") (pinfunction "1_1") (pintype "passive"))
      (node (ref "J8") (pin "17") (pinfunction "17_17") (pintype "passive"))
      (node (ref "Module1") (pin "84") (pinfunction "+3.3V_(Output)_84") (pintype "power_in"))
      (node (ref "Module1") (pin "86") (pinfunction "+3.3V_(Output)_86") (pintype "power_in"))
      (node (ref "R17") (pin "1") (pinfunction "1_1") (pintype "passive"))
      (node (ref "R21") (pin "2") (pinfunction "2_2") (pintype "passive"))
      (node (ref "R29") (pin "1") (pinfunction "1_1") (pintype "passive"))
      (node (ref "R5") (pin "1") (pinfunction "1_1") (pintype "passive"))
      (node (ref "U11") (pin "3") (pinfunction "VDD_3") (pintype "passive"))
      (node (ref "U13") (pin "1") (pinfunction "VCC_1") (pintype "power_in"))
      (node (ref "U18") (pin "5") (pinfunction "IN_5") (pintype "passive"))
      (node (ref "U3") (pin "15") (pinfunction "G_A_15") (pintype "passive"))
      (node (ref "U3") (pin "17") (pinfunction "Y_A_17") (pintype "passive"))
      (node (ref "U5") (pin "5") (pinfunction "VCC_5") (pintype "passive"))
      (node (ref "U6") (pin "10") (pinfunction "VDDA33_10") (pintype "power_in"))
      (node (ref "U6") (pin "15") (pinfunction "VDD33_15") (pintype "power_in"))
      (node (ref "U6") (pin "23") (pinfunction "VDD33_23") (pintype "power_in"))
      (node (ref "U6") (pin "27") (pinfunction "VBUS_DET_27") (pintype "input"))
      (node (ref "U6") (pin "29") (pinfunction "VDDA33_29") (pintype "power_in"))
      (node (ref "U6") (pin "36") (pinfunction "VDDA33_36") (pintype "power_in"))
      (node (ref "U6") (pin "5") (pinfunction "VDDA33_5") (pintype "power_in"))
    )
    (net (code "3") (name "+3.3V_PCIe") (class "Default")
      (node (ref "C30") (pin "1") (pinfunction "1_1") (pintype "passive"))
      (node (ref "C31") (pin "1") (pinfunction "1_1") (pintype "passive"))
      (node (ref "C32") (pin "1") (pinfunction "1_1") (pintype "passive"))
      (node (ref "C33") (pin "1") (pinfunction "1_1") (pintype "passive"))
      (node (ref "C45") (pin "1") (pinfunction "1_1") (pintype "passive"))
      (node (ref "C65") (pin "1") (pinfunction "1_1") (pintype "passive"))
      (node (ref "J12") (pin "A10") (pinfunction "+3.3V_A10") (pintype "passive"))
      (node (ref "J12") (pin "A5") (pinfunction "TCK_A5") (pintype "passive"))
      (node (ref "J12") (pin "A6") (pinfunction "TDI_A6") (pintype "passive"))
      (node (ref "J12") (pin "A8") (pinfunction "TMS_A8") (pintype "passive"))
      (node (ref "J12") (pin "A9") (pinfunction "+3.3V_A9") (pintype "passive"))
      (node (ref "J12") (pin "B10") (pinfunction "+3.3V_AUX_B10") (pintype "passive"))
      (node (ref "J12") (pin "B8") (pinfunction "+3.3V_B8") (pintype "passive"))
      (node (ref "J12") (pin "B9") (pinfunction "nTRST_B9") (pintype "passive"))
      (node (ref "L3") (pin "2") (pinfunction "2_2") (pintype "passive"))
      (node (ref "R24") (pin "1") (pinfunction "1_1") (pintype "passive"))
      (node (ref "TP1") (pin "1") (pinfunction "1_1") (pintype "passive"))
    )
    (net (code "4") (name "+5V") (class "Default")
      (node (ref "C18") (pin "1") (pinfunction "1_1") (pintype "passive"))
      (node (ref "C2") (pin "1") (pinfunction "1_1") (pintype "passive"))
      (node (ref "C22") (pin "1") (pinfunction "1_1") (pintype "passive"))
      (node (ref "C47") (pin "1") (pinfunction "1_1") (pintype "passive"))
      (node (ref "C49") (pin "1") (pinfunction "1_1") (pintype "passive"))
      (node (ref "C51") (pin "1") (pinfunction "1_1") (pintype "passive"))
      (node (ref "C52") (pin "1") (pinfunction "1_1") (pintype "passive"))
      (node (ref "C61") (pin "1") (pinfunction "1_1") (pintype "passive"))
      (node (ref "J20") (pin "4") (pinfunction "4_4") (pintype "passive"))
      (node (ref "J8") (pin "2") (pinfunction "2_2") (pintype "passive"))
      (node (ref "J8") (pin "4") (pinfunction "4_4") (pintype "passive"))
      (node (ref "L5") (pin "2") (pinfunction "2_2") (pintype "passive"))
      (node (ref "Module1") (pin "77") (pinfunction "+5V_(Input)_77") (pintype "power_in"))
      (node (ref "Module1") (pin "79") (pinfunction "+5V_(Input)_79") (pintype "power_in"))
      (node (ref "Module1") (pin "81") (pinfunction "+5V_(Input)_81") (pintype "power_in"))
      (node (ref "Module1") (pin "83") (pinfunction "+5V_(Input)_83") (pintype "power_in"))
      (node (ref "Module1") (pin "85") (pinfunction "+5V_(Input)_85") (pintype "power_in"))
      (node (ref "Module1") (pin "87") (pinfunction "+5V_(Input)_87") (pintype "power_in"))
      (node (ref "R19") (pin "2") (pinfunction "2_2") (pintype "passive"))
      (node (ref "R20") (pin "2") (pinfunction "2_2") (pintype "passive"))
      (node (ref "R27") (pin "1") (pinfunction "1_1") (pintype "passive"))
      (node (ref "TP4") (pin "1") (pinfunction "1_1") (pintype "passive"))
      (node (ref "U14") (pin "5") (pinfunction "VCC_5") (pintype "passive"))
      (node (ref "U7") (pin "1") (pinfunction "IN_1") (pintype "passive"))
      (node (ref "U9") (pin "5") (pinfunction "VCC_5") (pintype "passive"))
    )
    (net (code "5") (name "+12V") (class "Default")
      (node (ref "C25") (pin "1") (pinfunction "1_1") (pintype "passive"))
      (node (ref "C26") (pin "1") (pinfunction "1_1") (pintype "passive"))
      (node (ref "C27") (pin "1") (pinfunction "1_1") (pintype "passive"))
      (node (ref "C28") (pin "1") (pinfunction "1_1") (pintype "passive"))
      (node (ref "C34") (pin "1") (pinfunction "1_1") (pintype "passive"))
      (node (ref "C35") (pin "1") (pinfunction "1_1") (pintype "passive"))
      (node (ref "C37") (pin "1") (pinfunction "1_1") (pintype "passive"))
      (node (ref "C38") (pin "1") (pinfunction "1_1") (pintype "passive"))
      (node (ref "C39") (pin "1") (pinfunction "1_1") (pintype "passive"))
      (node (ref "C40") (pin "1") (pinfunction "1_1") (pintype "passive"))
      (node (ref "C41") (pin "1") (pinfunction "1_1") (pintype "passive"))
      (node (ref "C42") (pin "1") (pinfunction "1_1") (pintype "passive"))
      (node (ref "C43") (pin "1") (pinfunction "1_1") (pintype "passive"))
      (node (ref "C44") (pin "1") (pinfunction "1_1") (pintype "passive"))
      (node (ref "D4") (pin "1") (pinfunction "K_1") (pintype "passive"))
      (node (ref "J12") (pin "A2") (pinfunction "+12V_A2") (pintype "passive"))
      (node (ref "J12") (pin "A3") (pinfunction "+12V_A3") (pintype "passive"))
      (node (ref "J12") (pin "B1") (pinfunction "+12V_B1") (pintype "passive"))
      (node (ref "J12") (pin "B2") (pinfunction "+12V_B2") (pintype "passive"))
      (node (ref "J12") (pin "B3") (pinfunction "+12V_B3") (pintype "passive"))
      (node (ref "J17") (pin "2") (pinfunction "2_2") (pintype "passive"))
      (node (ref "J20") (pin "1") (pinfunction "1_1") (pintype "passive"))
      (node (ref "Q1") (pin "1") (pinfunction "S_1") (pintype "passive"))
      (node (ref "Q1") (pin "2") (pinfunction "S_2") (pintype "passive"))
      (node (ref "Q1") (pin "3") (pinfunction "S_3") (pintype "passive"))
      (node (ref "TP2") (pin "1") (pinfunction "1_1") (pintype "passive"))
      (node (ref "U15") (pin "2") (pinfunction "VIN_2") (pintype "passive"))
      (node (ref "U15") (pin "3") (pinfunction "EN_3") (pintype "passive"))
      (node (ref "U16") (pin "2") (pinfunction "VIN_2") (pintype "passive"))
      (node (ref "U16") (pin "3") (pinfunction "EN_3") (pintype "passive"))
    )
    (net (code "6") (name "/AIN0") (class "Default")
      (node (ref "J2") (pin "5") (pinfunction "5_5") (pintype "passive"))
      (node (ref "Module1") (pin "96") (pinfunction "AnalogIP0_96") (pintype "power_in"))
    )
    (net (code "7") (name "/AIN1") (class "Default")
      (node (ref "J2") (pin "6") (pinfunction "6_6") (pintype "passive"))
      (node (ref "Module1") (pin "94") (pinfunction "AnalogIP1_94") (pintype "power_in"))
    )
    (net (code "8") (name "/BT_nDis") (class "Default")
      (node (ref "J3") (pin "3") (pinfunction "3_3") (pintype "passive"))
      (node (ref "Module1") (pin "91") (pinfunction "BT_nDisable_91") (pintype "power_in"))
    )
    (net (code "9") (name "/CAM0_C_N") (class "Default")
      (node (ref "J4") (pin "8") (pinfunction "8_8") (pintype "passive"))
      (node (ref "Module1") (pin "140") (pinfunction "CAM0_C_N_140") (pintype "power_in"))
    )
    (net (code "10") (name "/CAM0_C_P") (class "Default")
      (node (ref "J4") (pin "9") (pinfunction "9_9") (pintype "passive"))
      (node (ref "Module1") (pin "142") (pinfunction "CAM0_C_P_142") (pintype "power_in"))
    )
    (net (code "11") (name "/CAM0_D0_N") (class "Default")
      (node (ref "J4") (pin "2") (pinfunction "2_2") (pintype "passive"))
      (node (ref "Module1") (pin "128") (pinfunction "CAM0_D0_N_128") (pintype "power_in"))
    )
    (net (code "12") (name "/CAM0_D0_P") (class "Default")
      (node (ref "J4") (pin "3") (pinfunction "3_3") (pintype "passive"))
      (node (ref "Module1") (pin "130") (pinfunction "CAM0_D0_P_130") (pintype "power_in"))
    )
    (net (code "13") (name "/CAM0_D1_N") (class "Default")
      (node (ref "J4") (pin "5") (pinfunction "5_5") (pintype "passive"))
      (node (ref "Module1") (pin "134") (pinfunction "CAM0_D1_N_134") (pintype "power_in"))
    )
    (net (code "14") (name "/CAM0_D1_P") (class "Default")
      (node (ref "J4") (pin "6") (pinfunction "6_6") (pintype "passive"))
      (node (ref "Module1") (pin "136") (pinfunction "CAM0_D1_P_136") (pintype "power_in"))
    )
    (net (code "15") (name "/CAM1_C_N") (class "Default")
      (node (ref "J5") (pin "8") (pinfunction "8_8") (pintype "passive"))
      (node (ref "Module1") (pin "127") (pinfunction "CAM1_C_N_127") (pintype "power_in"))
    )
    (net (code "16") (name "/CAM1_C_P") (class "Default")
      (node (ref "J5") (pin "9") (pinfunction "9_9") (pintype "passive"))
      (node (ref "Module1") (pin "129") (pinfunction "CAM1_C_P_129") (pintype "power_in"))
    )
    (net (code "17") (name "/CAM1_D0_N") (class "Default")
      (node (ref "J5") (pin "2") (pinfunction "2_2") (pintype "passive"))
      (node (ref "Module1") (pin "115") (pinfunction "CAM1_D0_N_115") (pintype "power_in"))
    )
    (net (code "18") (name "/CAM1_D0_P") (class "Default")
      (node (ref "J5") (pin "3") (pinfunction "3_3") (pintype "passive"))
      (node (ref "Module1") (pin "117") (pinfunction "CAM1_D0_P_117") (pintype "power_in"))
    )
    (net (code "19") (name "/CAM1_D1_N") (class "Default")
      (node (ref "J5") (pin "5") (pinfunction "5_5") (pintype "passive"))
      (node (ref "Module1") (pin "121") (pinfunction "CAM1_D1_N_121") (pintype "power_in"))
    )
    (net (code "20") (name "/CAM1_D1_P") (class "Default")
      (node (ref "J5") (pin "6") (pinfunction "6_6") (pintype "passive"))
      (node (ref "Module1") (pin "123") (pinfunction "CAM1_D1_P_123") (pintype "power_in"))
    )
    (net (code "21") (name "/CAM1_D2_N") (class "Default")
      (node (ref "J5") (pin "11") (pinfunction "11_11") (pintype "passive"))
      (node (ref "Module1") (pin "133") (pinfunction "CAM1_D2_N_133") (pintype "power_in"))
    )
    (net (code "22") (name "/CAM1_D2_P") (class "Default")
      (node (ref "J5") (pin "12") (pinfunction "12_12") (pintype "passive"))
      (node (ref "Module1") (pin "135") (pinfunction "CAM1_D2_P_135") (pintype "power_in"))
    )
    (net (code "23") (name "/CAM1_D3_N") (class "Default")
      (node (ref "J5") (pin "14") (pinfunction "14_14") (pintype "passive"))
      (node (ref "Module1") (pin "139") (pinfunction "CAM1_D3_N_139") (pintype "power_in"))
    )
    (net (code "24") (name "/CAM1_D3_P") (class "Default")
      (node (ref "J5") (pin "15") (pinfunction "15_15") (pintype "passive"))
      (node (ref "Module1") (pin "141") (pinfunction "CAM1_D3_P_141") (pintype "power_in"))
    )
    (net (code "25") (name "/CAM_GPIO") (class "Default")
      (node (ref "J4") (pin "17") (pinfunction "17_17") (pintype "passive"))
      (node (ref "J5") (pin "17") (pinfunction "17_17") (pintype "passive"))
      (node (ref "Module1") (pin "97") (pinfunction "Camera_GPIO_97") (pintype "power_in"))
    )
    (net (code "26") (name "/DSI0_C_N") (class "Default")
      (node (ref "J15") (pin "8") (pinfunction "8_8") (pintype "passive"))
      (node (ref "Module1") (pin "169") (pinfunction "DSI0_C_N_169") (pintype "power_in"))
    )
    (net (code "27") (name "/DSI0_C_P") (class "Default")
      (node (ref "J15") (pin "9") (pinfunction "9_9") (pintype "passive"))
      (node (ref "Module1") (pin "171") (pinfunction "DSI0_C_P_171") (pintype "power_in"))
    )
    (net (code "28") (name "/DSI0_D0_N") (class "Default")
      (node (ref "J15") (pin "2") (pinfunction "2_2") (pintype "passive"))
      (node (ref "Module1") (pin "157") (pinfunction "DSI0_D0_N_157") (pintype "power_in"))
    )
    (net (code "29") (name "/DSI0_D0_P") (class "Default")
      (node (ref "J15") (pin "3") (pinfunction "3_3") (pintype "passive"))
      (node (ref "Module1") (pin "159") (pinfunction "DSI0_D0_P_159") (pintype "power_in"))
    )
    (net (code "30") (name "/DSI0_D1_N") (class "Default")
      (node (ref "J15") (pin "5") (pinfunction "5_5") (pintype "passive"))
      (node (ref "Module1") (pin "163") (pinfunction "DSI0_D1_N_163") (pintype "power_in"))
    )
    (net (code "31") (name "/DSI0_D1_P") (class "Default")
      (node (ref "J15") (pin "6") (pinfunction "6_6") (pintype "passive"))
      (node (ref "Module1") (pin "165") (pinfunction "DSI0_D1_P_165") (pintype "power_in"))
    )
    (net (code "32") (name "/DSI1_C_N") (class "Default")
      (node (ref "J16") (pin "8") (pinfunction "8_8") (pintype "passive"))
      (node (ref "Module1") (pin "187") (pinfunction "DSI1_C_N_187") (pintype "power_in"))
    )
    (net (code "33") (name "/DSI1_C_P") (class "Default")
      (node (ref "J16") (pin "9") (pinfunction "9_9") (pintype "passive"))
      (node (ref "Module1") (pin "189") (pinfunction "DSI1_C_P_189") (pintype "power_in"))
    )
    (net (code "34") (name "/DSI1_D0_N") (class "Default")
      (node (ref "J16") (pin "2") (pinfunction "2_2") (pintype "passive"))
      (node (ref "Module1") (pin "175") (pinfunction "DSI1_D0_N_175") (pintype "power_in"))
    )
    (net (code "35") (name "/DSI1_D0_P") (class "Default")
      (node (ref "J16") (pin "3") (pinfunction "3_3") (pintype "passive"))
      (node (ref "Module1") (pin "177") (pinfunction "DSI1_D0_P_177") (pintype "power_in"))
    )
    (net (code "36") (name "/DSI1_D1_N") (class "Default")
      (node (ref "J16") (pin "5") (pinfunction "5_5") (pintype "passive"))
      (node (ref "Module1") (pin "181") (pinfunction "DSI1_D1_N_181") (pintype "power_in"))
    )
    (net (code "37") (name "/DSI1_D1_P") (class "Default")
      (node (ref "J16") (pin "6") (pinfunction "6_6") (pintype "passive"))
      (node (ref "Module1") (pin "183") (pinfunction "DSI1_D1_P_183") (pintype "power_in"))
    )
    (net (code "38") (name "/DSI1_D2_N") (class "Default")
      (node (ref "J16") (pin "11") (pinfunction "11_11") (pintype "passive"))
      (node (ref "Module1") (pin "193") (pinfunction "DSI1_D2_N_193") (pintype "power_in"))
    )
    (net (code "39") (name "/DSI1_D2_P") (class "Default")
      (node (ref "J16") (pin "12") (pinfunction "12_12") (pintype "passive"))
      (node (ref "Module1") (pin "195") (pinfunction "DSI1_D2_P_195") (pintype "power_in"))
    )
    (net (code "40") (name "/DSI1_D3_N") (class "Default")
      (node (ref "J16") (pin "14") (pinfunction "14_14") (pintype "passive"))
      (node (ref "Module1") (pin "194") (pinfunction "DSI1_D3_N_194") (pintype "power_in"))
    )
    (net (code "41") (name "/DSI1_D3_P") (class "Default")
      (node (ref "J16") (pin "15") (pinfunction "15_15") (pintype "passive"))
      (node (ref "Module1") (pin "196") (pinfunction "DSI1_D3_P_196") (pintype "power_in"))
    )
    (net (code "42") (name "/EEPROM_nWP") (class "Default")
      (node (ref "J2") (pin "4") (pinfunction "4_4") (pintype "passive"))
      (node (ref "Module1") (pin "20") (pinfunction "EEPROM_nWP_20") (pintype "power_in"))
    )
    (net (code "43") (name "/ETH_LEDG") (class "Default")
      (node (ref "Module1") (pin "17") (pinfunction "Ethernet_nLED2(3.3V)_17") (pintype "power_in"))
      (node (ref "R2") (pin "2") (pinfunction "2_2") (pintype "passive"))
    )
    (net (code "44") (name "/ETH_LEDY") (class "Default")
      (node (ref "Module1") (pin "15") (pinfunction "Ethernet_nLED3(3.3V)_15") (pintype "power_in"))
      (node (ref "R3") (pin "2") (pinfunction "2_2") (pintype "passive"))
    )
    (net (code "45") (name "/GLOBAL_EN") (class "Default")
      (node (ref "J1") (pin "1") (pinfunction "1_1") (pintype "passive"))
      (node (ref "J2") (pin "14") (pinfunction "14_14") (pintype "passive"))
      (node (ref "Module1") (pin "99") (pinfunction "Global_EN_99") (pintype "power_in"))
      (node (ref "U14") (pin "4") (pinfunction "Y_4") (pintype "passive"))
    )
    (net (code "46") (name "/GPIO2") (class "Default")
      (node (ref "J8") (pin "3") (pinfunction "3_3") (pintype "passive"))
      (node (ref "Module1") (pin "58") (pinfunction "GPIO2_58") (pintype "power_in"))
    )
    (net (code "47") (name "/GPIO3") (class "Default")
      (node (ref "J8") (pin "5") (pinfunction "5_5") (pintype "passive"))
      (node (ref "Module1") (pin "56") (pinfunction "GPIO3_56") (pintype "power_in"))
    )
    (net (code "48") (name "/GPIO4") (class "Default")
      (node (ref "J8") (pin "7") (pinfunction "7_7") (pintype "passive"))
      (node (ref "Module1") (pin "54") (pinfunction "GPIO4_54") (pintype "power_in"))
    )
    (net (code "49") (name "/GPIO5") (class "Default")
      (node (ref "J8") (pin "29") (pinfunction "29_29") (pintype "passive"))
      (node (ref "Module1") (pin "34") (pinfunction "GPIO5_34") (pintype "power_in"))
    )
    (net (code "50") (name "/GPIO6") (class "Default")
      (node (ref "J8") (pin "31") (pinfunction "31_31") (pintype "passive"))
      (node (ref "Module1") (pin "30") (pinfunction "GPIO6_30") (pintype "power_in"))
    )
    (net (code "51") (name "/GPIO7") (class "Default")
      (node (ref "J8") (pin "26") (pinfunction "26_26") (pintype "passive"))
      (node (ref "Module1") (pin "37") (pinfunction "GPIO7_37") (pintype "power_in"))
    )
    (net (code "52") (name "/GPIO8") (class "Default")
      (node (ref "J8") (pin "24") (pinfunction "24_24") (pintype "passive"))
      (node (ref "Module1") (pin "39") (pinfunction "GPIO8_39") (pintype "power_in"))
    )
    (net (code "53") (name "/GPIO9") (class "Default")
      (node (ref "J8") (pin "21") (pinfunction "21_21") (pintype "passive"))
      (node (ref "Module1") (pin "40") (pinfunction "GPIO9_40") (pintype "power_in"))
    )
    (net (code "54") (name "/GPIO10") (class "Default")
      (node (ref "J8") (pin "19") (pinfunction "19_19") (pintype "passive"))
      (node (ref "Module1") (pin "44") (pinfunction "GPIO10_44") (pintype "power_in"))
    )
    (net (code "55") (name "/GPIO11") (class "Default")
      (node (ref "J8") (pin "23") (pinfunction "23_23") (pintype "passive"))
      (node (ref "Module1") (pin "38") (pinfunction "GPIO11_38") (pintype "power_in"))
    )
    (net (code "56") (name "/GPIO12") (class "Default")
      (node (ref "J8") (pin "32") (pinfunction "32_32") (pintype "passive"))
      (node (ref "Module1") (pin "31") (pinfunction "GPIO12_31") (pintype "power_in"))
    )
    (net (code "57") (name "/GPIO13") (class "Default")
      (node (ref "J8") (pin "33") (pinfunction "33_33") (pintype "passive"))
      (node (ref "Module1") (pin "28") (pinfunction "GPIO13_28") (pintype "power_in"))
    )
    (net (code "58") (name "/GPIO14") (class "Default")
      (node (ref "J8") (pin "8") (pinfunction "8_8") (pintype "passive"))
      (node (ref "Module1") (pin "55") (pinfunction "GPIO14_55") (pintype "power_in"))
    )
    (net (code "59") (name "/GPIO15") (class "Default")
      (node (ref "J8") (pin "10") (pinfunction "10_10") (pintype "passive"))
      (node (ref "Module1") (pin "51") (pinfunction "GPIO15_51") (pintype "power_in"))
    )
    (net (code "60") (name "/GPIO16") (class "Default")
      (node (ref "J8") (pin "36") (pinfunction "36_36") (pintype "passive"))
      (node (ref "Module1") (pin "29") (pinfunction "GPIO16_29") (pintype "power_in"))
    )
    (net (code "61") (name "/GPIO17") (class "Default")
      (node (ref "J8") (pin "11") (pinfunction "11_11") (pintype "passive"))
      (node (ref "Module1") (pin "50") (pinfunction "GPIO17_50") (pintype "power_in"))
    )
    (net (code "62") (name "/GPIO18") (class "Default")
      (node (ref "J8") (pin "12") (pinfunction "12_12") (pintype "passive"))
      (node (ref "Module1") (pin "49") (pinfunction "GPIO18_49") (pintype "power_in"))
    )
    (net (code "63") (name "/GPIO19") (class "Default")
      (node (ref "J8") (pin "35") (pinfunction "35_35") (pintype "passive"))
      (node (ref "Module1") (pin "26") (pinfunction "GPIO19_26") (pintype "power_in"))
    )
    (net (code "64") (name "/GPIO20") (class "Default")
      (node (ref "J8") (pin "38") (pinfunction "38_38") (pintype "passive"))
      (node (ref "Module1") (pin "27") (pinfunction "GPIO20_27") (pintype "power_in"))
    )
    (net (code "65") (name "/GPIO21") (class "Default")
      (node (ref "J8") (pin "40") (pinfunction "40_40") (pintype "passive"))
      (node (ref "Module1") (pin "25") (pinfunction "GPIO21_25") (pintype "power_in"))
    )
    (net (code "66") (name "/GPIO22") (class "Default")
      (node (ref "J8") (pin "15") (pinfunction "15_15") (pintype "passive"))
      (node (ref "Module1") (pin "46") (pinfunction "GPIO22_46") (pintype "power_in"))
    )
    (net (code "67") (name "/GPIO23") (class "Default")
      (node (ref "J8") (pin "16") (pinfunction "16_16") (pintype "passive"))
      (node (ref "Module1") (pin "47") (pinfunction "GPIO23_47") (pintype "power_in"))
    )
    (net (code "68") (name "/GPIO24") (class "Default")
      (node (ref "J8") (pin "18") (pinfunction "18_18") (pintype "passive"))
      (node (ref "Module1") (pin "45") (pinfunction "GPIO24_45") (pintype "power_in"))
    )
    (net (code "69") (name "/GPIO25") (class "Default")
      (node (ref "J8") (pin "22") (pinfunction "22_22") (pintype "passive"))
      (node (ref "Module1") (pin "41") (pinfunction "GPIO25_41") (pintype "power_in"))
    )
    (net (code "70") (name "/GPIO26") (class "Default")
      (node (ref "J8") (pin "37") (pinfunction "37_37") (pintype "passive"))
      (node (ref "Module1") (pin "24") (pinfunction "GPIO26_24") (pintype "power_in"))
    )
    (net (code "71") (name "/GPIO27") (class "Default")
      (node (ref "J8") (pin "13") (pinfunction "13_13") (pintype "passive"))
      (node (ref "Module1") (pin "48") (pinfunction "GPIO27_48") (pintype "power_in"))
    )
    (net (code "72") (name "/GPIO_VREF") (class "Default")
      (node (ref "Module1") (pin "78") (pinfunction "GPIO_VREF(1.8V/3.3V_Input)_78") (pintype "power_in"))
      (node (ref "R4") (pin "2") (pinfunction "2_2") (pintype "passive"))
      (node (ref "R5") (pin "2") (pinfunction "2_2") (pintype "passive"))
      (node (ref "R6") (pin "1") (pinfunction "1_1") (pintype "passive"))
      (node (ref "R7") (pin "1") (pinfunction "1_1") (pintype "passive"))
    )
    (net (code "73") (name "/HD1_N") (class "Default")
      (node (ref "J13") (pin "2") (pinfunction "D-_1_2") (pintype "passive"))
      (node (ref "U6") (pin "1") (pinfunction "USBDM_DN1/PRT_DIS_M1_1") (pintype "bidirectional"))
    )
    (net (code "74") (name "/HD1_P") (class "Default")
      (node (ref "J13") (pin "3") (pinfunction "D+_1_3") (pintype "passive"))
      (node (ref "U6") (pin "2") (pinfunction "USBDP_DN1/PRT_DIS_P1_2") (pintype "bidirectional"))
    )
    (net (code "75") (name "/HD2_N") (class "Default")
      (node (ref "J13") (pin "6") (pinfunction "D-_2_6") (pintype "passive"))
      (node (ref "U6") (pin "3") (pinfunction "USBDM_DN2/PRT_DIS_M2_3") (pintype "bidirectional"))
    )
    (net (code "76") (name "/HD2_P") (class "Default")
      (node (ref "J13") (pin "7") (pinfunction "D+_2_7") (pintype "passive"))
      (node (ref "U6") (pin "4") (pinfunction "USBDP_DN2/PRT_DIS_P2_4") (pintype "bidirectional"))
    )
    (net (code "77") (name "/HD3_N") (class "Default")
      (node (ref "U6") (pin "6") (pinfunction "USBDM_DN3/PRT_DIS_M3_6") (pintype "bidirectional"))
    )
    (net (code "78") (name "/HD3_P") (class "Default")
      (node (ref "U6") (pin "7") (pinfunction "USBDP_DN3/PRT_DIS_P3_7") (pintype "bidirectional"))
    )
    (net (code "79") (name "/HD4_N") (class "Default")
      (node (ref "U6") (pin "8") (pinfunction "USBDM_DN4/PRT_DIS_M4_8") (pintype "bidirectional"))
    )
    (net (code "80") (name "/HD4_P") (class "Default")
      (node (ref "U6") (pin "9") (pinfunction "USBDP_DN4/PRT_DIS_P4_9") (pintype "bidirectional"))
    )
    (net (code "81") (name "/HDMI0_CEC") (class "Default")
      (node (ref "Module1") (pin "151") (pinfunction "HDMI0_CEC_151") (pintype "power_in"))
    )
    (net (code "82") (name "/HDMI0_CK_N") (class "Default")
      (node (ref "Module1") (pin "190") (pinfunction "HDMI0_CLK_N_190") (pintype "power_in"))
    )
    (net (code "83") (name "/HDMI0_CK_P") (class "Default")
      (node (ref "Module1") (pin "188") (pinfunction "HDMI0_CLK_P_188") (pintype "power_in"))
    )
    (net (code "84") (name "/HDMI0_D0_N") (class "Default")
      (node (ref "Module1") (pin "184") (pinfunction "HDMI0_TX0_N_184") (pintype "power_in"))
    )
    (net (code "85") (name "/HDMI0_D0_P") (class "Default")
      (node (ref "Module1") (pin "182") (pinfunction "HDMI0_TX0_P_182") (pintype "power_in"))
    )
    (net (code "86") (name "/HDMI0_D1_N") (class "Default")
      (node (ref "Module1") (pin "178") (pinfunction "HDMI0_TX1_N_178") (pintype "power_in"))
    )
    (net (code "87") (name "/HDMI0_D1_P") (class "Default")
      (node (ref "Module1") (pin "176") (pinfunction "HDMI0_TX1_P_176") (pintype "power_in"))
    )
    (net (code "88") (name "/HDMI0_D2_N") (class "Default")
      (node (ref "Module1") (pin "172") (pinfunction "HDMI0_TX2_N_172") (pintype "power_in"))
    )
    (net (code "89") (name "/HDMI0_D2_P") (class "Default")
      (node (ref "Module1") (pin "170") (pinfunction "HDMI0_TX2_P_170") (pintype "power_in"))
    )
    (net (code "90") (name "/HDMI0_HOTPLUG") (class "Default")
      (node (ref "Module1") (pin "153") (pinfunction "HDMI0_HOTPLUG_153") (pintype "power_in"))
    )
    (net (code "91") (name "/HDMI0_SCL") (class "Default")
      (node (ref "Module1") (pin "200") (pinfunction "HDMI0_SCL_200") (pintype "power_in"))
    )
    (net (code "92") (name "/HDMI0_SDA") (class "Default")
      (node (ref "Module1") (pin "199") (pinfunction "HDMI0_SDA_199") (pintype "power_in"))
    )
    (net (code "93") (name "/HDMI1_CEC") (class "Default")
      (node (ref "Module1") (pin "149") (pinfunction "HDMI1_CEC_149") (pintype "power_in"))
    )
    (net (code "94") (name "/HDMI1_CK_N") (class "Default")
      (node (ref "Module1") (pin "166") (pinfunction "HDMI1_CLK_N_166") (pintype "power_in"))
    )
    (net (code "95") (name "/HDMI1_CK_P") (class "Default")
      (node (ref "Module1") (pin "164") (pinfunction "HDMI1_CLK_P_164") (pintype "power_in"))
    )
    (net (code "96") (name "/HDMI1_D0_N") (class "Default")
      (node (ref "Module1") (pin "160") (pinfunction "HDMI1_TX0_N_160") (pintype "power_in"))
    )
    (net (code "97") (name "/HDMI1_D0_P") (class "Default")
      (node (ref "Module1") (pin "158") (pinfunction "HDMI1_TX0_P_158") (pintype "power_in"))
    )
    (net (code "98") (name "/HDMI1_D1_N") (class "Default")
      (node (ref "Module1") (pin "154") (pinfunction "HDMI1_TX1_N_154") (pintype "power_in"))
    )
    (net (code "99") (name "/HDMI1_D1_P") (class "Default")
      (node (ref "Module1") (pin "152") (pinfunction "HDMI1_TX1_P_152") (pintype "power_in"))
    )
    (net (code "100") (name "/HDMI1_D2_N") (class "Default")
      (node (ref "Module1") (pin "148") (pinfunction "HDMI1_TX2_N_148") (pintype "power_in"))
    )
    (net (code "101") (name "/HDMI1_D2_P") (class "Default")
      (node (ref "Module1") (pin "146") (pinfunction "HDMI1_TX2_P_146") (pintype "power_in"))
    )
    (net (code "102") (name "/HDMI1_HOTPLUG") (class "Default")
      (node (ref "Module1") (pin "143") (pinfunction "HDMI1_HOTPLUG_143") (pintype "power_in"))
    )
    (net (code "103") (name "/HDMI1_SCL") (class "Default")
      (node (ref "Module1") (pin "147") (pinfunction "HDMI1_SCL_147") (pintype "power_in"))
    )
    (net (code "104") (name "/HDMI1_SDA") (class "Default")
      (node (ref "Module1") (pin "145") (pinfunction "HDMI1_SDA_145") (pintype "power_in"))
    )
    (net (code "105") (name "/ID_SC") (class "Default")
      (node (ref "J6") (pin "1") (pinfunction "1_1") (pintype "passive"))
      (node (ref "J8") (pin "28") (pinfunction "28_28") (pintype "passive"))
      (node (ref "Module1") (pin "35") (pinfunction "ID_SC_35") (pintype "power_in"))
    )
    (net (code "106") (name "/ID_SD") (class "Default")
      (node (ref "J6") (pin "3") (pinfunction "3_3") (pintype "passive"))
      (node (ref "J8") (pin "27") (pinfunction "27_27") (pintype "passive"))
      (node (ref "Module1") (pin "36") (pinfunction "ID_SD_36") (pintype "power_in"))
    )
    (net (code "107") (name "/PCIe_CLK_N") (class "Default")
      (node (ref "J12") (pin "A14") (pinfunction "REFCLK-_A14") (pintype "passive"))
      (node (ref "Module1") (pin "112") (pinfunction "PCIe_CLK_P_112") (pintype "power_in"))
    )
    (net (code "108") (name "/PCIe_CLK_P") (class "Default")
      (node (ref "J12") (pin "A13") (pinfunction "REFCLK+_A13") (pintype "passive"))
      (node (ref "Module1") (pin "110") (pinfunction "PCIe_CLK_P_110") (pintype "power_in"))
    )
    (net (code "109") (name "/PCIe_CLK_nREQ") (class "Default")
      (node (ref "J12") (pin "B12") (pinfunction "nCLKREQ_B12") (pintype "passive"))
      (node (ref "Module1") (pin "102") (pinfunction "PCIe_CLK_nREQ_102") (pintype "power_in"))
    )
    (net (code "110") (name "/PCIe_RX_N") (class "Default")
      (node (ref "J12") (pin "A16") (pinfunction "PERP0_A16") (pintype "passive"))
      (node (ref "Module1") (pin "118") (pinfunction "PCIe_RX_P_118") (pintype "power_in"))
    )
    (net (code "111") (name "/PCIe_RX_P") (class "Default")
      (node (ref "J12") (pin "A17") (pinfunction "PERN0_A17") (pintype "passive"))
      (node (ref "Module1") (pin "116") (pinfunction "PCIe_RX_P_116") (pintype "power_in"))
    )
    (net (code "112") (name "/PCIe_TX_N") (class "Default")
      (node (ref "J12") (pin "B14") (pinfunction "PETP0_B14") (pintype "passive"))
      (node (ref "Module1") (pin "124") (pinfunction "PCIe_TX_P_124") (pintype "power_in"))
    )
    (net (code "113") (name "/PCIe_TX_P") (class "Default")
      (node (ref "J12") (pin "B15") (pinfunction "PETN0_B15") (pintype "passive"))
      (node (ref "Module1") (pin "122") (pinfunction "PCIe_TX_P_122") (pintype "power_in"))
    )
    (net (code "114") (name "/PCIe_nRST") (class "Default")
      (node (ref "J12") (pin "A11") (pinfunction "nPERST_A11") (pintype "passive"))
      (node (ref "Module1") (pin "109") (pinfunction "PCIe_nRST_109") (pintype "power_in"))
    )
    (net (code "115") (name "/PWR1") (class "Default")
      (node (ref "U6") (pin "12") (pinfunction "PRTPWR1/BC_EN1_12") (pintype "input"))
      (node (ref "U7") (pin "3") (pinfunction "EN_3") (pintype "passive"))
    )
    (net (code "116") (name "/RUN_PG") (class "Default")
      (node (ref "J1") (pin "3") (pinfunction "3_3") (pintype "passive"))
      (node (ref "Module1") (pin "92") (pinfunction "RUN_PG_92") (pintype "power_in"))
      (node (ref "U9") (pin "2") (pinfunction "A_2") (pintype "passive"))
    )
    (net (code "117") (name "/Reserved") (class "Default")
      (node (ref "Module1") (pin "76") (pinfunction "Reserved_76") (pintype "power_in"))
      (node (ref "R18") (pin "1") (pinfunction "1_1") (pintype "passive"))
    )
    (net (code "118") (name "/SCL0") (class "Default")
      (node (ref "J16") (pin "20") (pinfunction "20_20") (pintype "passive"))
      (node (ref "J5") (pin "20") (pinfunction "20_20") (pintype "passive"))
      (node (ref "Module1") (pin "80") (pinfunction "SCL0_80") (pintype "power_in"))
      (node (ref "U11") (pin "2") (pinfunction "SCL_2") (pintype "passive"))
      (node (ref "U8") (pin "6") (pinfunction "SCL_6") (pintype "passive"))
    )
    (net (code "119") (name "/SCL1") (class "Default")
      (node (ref "J15") (pin "20") (pinfunction "20_20") (pintype "passive"))
      (node (ref "J4") (pin "20") (pinfunction "20_20") (pintype "passive"))
      (node (ref "J6") (pin "2") (pinfunction "2_2") (pintype "passive"))
      (node (ref "R7") (pin "2") (pinfunction "2_2") (pintype "passive"))
    )
    (net (code "120") (name "/SDA0") (class "Default")
      (node (ref "J16") (pin "21") (pinfunction "21_21") (pintype "passive"))
      (node (ref "J5") (pin "21") (pinfunction "21_21") (pintype "passive"))
      (node (ref "Module1") (pin "82") (pinfunction "SDA0_82") (pintype "power_in"))
      (node (ref "U11") (pin "1") (pinfunction "SDA_1") (pintype "passive"))
      (node (ref "U8") (pin "5") (pinfunction "SDA_5") (pintype "passive"))
    )
    (net (code "121") (name "/SDA1") (class "Default")
      (node (ref "J15") (pin "21") (pinfunction "21_21") (pintype "passive"))
      (node (ref "J4") (pin "21") (pinfunction "21_21") (pintype "passive"))
      (node (ref "J6") (pin "4") (pinfunction "4_4") (pintype "passive"))
      (node (ref "R6") (pin "2") (pinfunction "2_2") (pintype "passive"))
    )
    (net (code "122") (name "/SD_CLK") (class "Default")
      (node (ref "J7") (pin "5") (pinfunction "CLK_5") (pintype "passive"))
      (node (ref "Module1") (pin "57") (pinfunction "SD_CLK_57") (pintype "power_in"))
    )
    (net (code "123") (name "/SD_CMD") (class "Default")
      (node (ref "J7") (pin "3") (pinfunction "CMD_3") (pintype "passive"))
      (node (ref "Module1") (pin "62") (pinfunction "SD_CMD_62") (pintype "power_in"))
    )
    (net (code "124") (name "/SD_DAT0") (class "Default")
      (node (ref "J7") (pin "7") (pinfunction "DAT0_7") (pintype "passive"))
      (node (ref "Module1") (pin "63") (pinfunction "SD_DATA0_63") (pintype "power_in"))
    )
    (net (code "125") (name "/SD_DAT1") (class "Default")
      (node (ref "J7") (pin "8") (pinfunction "DAT1_8") (pintype "passive"))
      (node (ref "Module1") (pin "67") (pinfunction "SD_DATA1_67") (pintype "power_in"))
    )
    (net (code "126") (name "/SD_DAT2") (class "Default")
      (node (ref "J7") (pin "1") (pinfunction "DAT2_1") (pintype "passive"))
      (node (ref "Module1") (pin "69") (pinfunction "SD_DATA2_69") (pintype "power_in"))
    )
    (net (code "127") (name "/SD_DAT3") (class "Default")
      (node (ref "J7") (pin "2") (pinfunction "CD/DAT3^2_2") (pintype "passive"))
      (node (ref "Module1") (pin "61") (pinfunction "SD_DATA3_61") (pintype "power_in"))
    )
    (net (code "128") (name "/SD_PWR") (class "Default")
      (node (ref "C5") (pin "1") (pinfunction "1_1") (pintype "passive"))
      (node (ref "J7") (pin "4") (pinfunction "VDD_4") (pintype "power_in"))
      (node (ref "U18") (pin "1") (pinfunction "OUT_1") (pintype "passive"))
    )
    (net (code "129") (name "/SD_PWR_ON") (class "Default")
      (node (ref "Module1") (pin "75") (pinfunction "SD_PWR_ON_75") (pintype "power_in"))
      (node (ref "R29") (pin "2") (pinfunction "2_2") (pintype "passive"))
      (node (ref "U18") (pin "4") (pinfunction "EN_4") (pintype "passive"))
    )
    (net (code "130") (name "/SYNC_IN") (class "Default")
      (node (ref "J2") (pin "8") (pinfunction "8_8") (pintype "passive"))
      (node (ref "Module1") (pin "16") (pinfunction "Ethernet_SYNC_IN(1.8V)_16") (pintype "power_in"))
    )
    (net (code "131") (name "/SYNC_OUT") (class "Default")
      (node (ref "J2") (pin "9") (pinfunction "9_9") (pintype "passive"))
      (node (ref "Module1") (pin "18") (pinfunction "Ethernet_SYNC_OUT(1.8V)_18") (pintype "power_in"))
    )
    (net (code "132") (name "/TR0_TAP") (class "Default")
      (node (ref "J9") (pin "3") (pinfunction "3_3") (pintype "passive"))
      (node (ref "U3") (pin "11") (pinfunction "VC1_11") (pintype "passive"))
    )
    (net (code "133") (name "/TR1_TAP") (class "Default")
      (node (ref "J9") (pin "1") (pinfunction "1_1") (pintype "passive"))
      (node (ref "U3") (pin "12") (pinfunction "VC2_12") (pintype "passive"))
    )
    (net (code "134") (name "/TR2_TAP") (class "Default")
      (node (ref "J9") (pin "2") (pinfunction "2_2") (pintype "passive"))
      (node (ref "U3") (pin "13") (pinfunction "VC3_13") (pintype "passive"))
    )
    (net (code "135") (name "/TR3_TAP") (class "Default")
      (node (ref "J9") (pin "4") (pinfunction "4_4") (pintype "passive"))
      (node (ref "U3") (pin "14") (pinfunction "VC4_14") (pintype "passive"))
    )
    (net (code "136") (name "/TRD0_N") (class "Default")
      (node (ref "Module1") (pin "10") (pinfunction "Ethernet_Pair0_N_10") (pintype "power_in"))
      (node (ref "U2") (pin "4") (pinfunction "D2+_4") (pintype "passive"))
      (node (ref "U2") (pin "7") (pinfunction "NC_7_7") (pintype "passive"))
      (node (ref "U3") (pin "2") (pinfunction "TRD0-_2") (pintype "passive"))
    )
    (net (code "137") (name "/TRD0_P") (class "Default")
      (node (ref "Module1") (pin "12") (pinfunction "Ethernet_Pair0_P_12") (pintype "power_in"))
      (node (ref "U2") (pin "5") (pinfunction "D2-_5") (pintype "passive"))
      (node (ref "U2") (pin "6") (pinfunction "NC_6_6") (pintype "passive"))
      (node (ref "U3") (pin "1") (pinfunction "TRD0+_1") (pintype "passive"))
    )
    (net (code "138") (name "/TRD1_N") (class "Default")
      (node (ref "Module1") (pin "6") (pinfunction "Ethernet_Pair1_N_6") (pintype "power_in"))
      (node (ref "U2") (pin "2") (pinfunction "D1-_2") (pintype "passive"))
      (node (ref "U2") (pin "9") (pinfunction "NC_9_9") (pintype "passive"))
      (node (ref "U3") (pin "6") (pinfunction "TRD1-_6") (pintype "passive"))
    )
    (net (code "139") (name "/TRD1_P") (class "Default")
      (node (ref "Module1") (pin "4") (pinfunction "Ethernet_Pair1_P_4") (pintype "power_in"))
      (node (ref "U2") (pin "1") (pinfunction "D1+_1") (pintype "passive"))
      (node (ref "U2") (pin "10") (pinfunction "NC_10_10") (pintype "passive"))
      (node (ref "U3") (pin "3") (pinfunction "TRD1+_3") (pintype "passive"))
    )
    (net (code "140") (name "/TRD2_N") (class "Default")
      (node (ref "Module1") (pin "9") (pinfunction "Ethernet_Pair2_N_9") (pintype "power_in"))
      (node (ref "U1") (pin "4") (pinfunction "D2+_4") (pintype "passive"))
      (node (ref "U1") (pin "7") (pinfunction "NC_7_7") (pintype "passive"))
      (node (ref "U3") (pin "8") (pinfunction "TRD2-_8") (pintype "passive"))
    )
    (net (code "141") (name "/TRD2_P") (class "Default")
      (node (ref "Module1") (pin "11") (pinfunction "Ethernet_Pair2_P_11") (pintype "power_in"))
      (node (ref "U1") (pin "5") (pinfunction "D2-_5") (pintype "passive"))
      (node (ref "U1") (pin "6") (pinfunction "NC_6_6") (pintype "passive"))
      (node (ref "U3") (pin "7") (pinfunction "TRD2+_7") (pintype "passive"))
    )
    (net (code "142") (name "/TRD3_N") (class "Default")
      (node (ref "Module1") (pin "5") (pinfunction "Ethernet_Pair3_N_5") (pintype "power_in"))
      (node (ref "U1") (pin "2") (pinfunction "D1-_2") (pintype "passive"))
      (node (ref "U1") (pin "9") (pinfunction "NC_9_9") (pintype "passive"))
      (node (ref "U3") (pin "10") (pinfunction "TRD3-_10") (pintype "passive"))
    )
    (net (code "143") (name "/TRD3_P") (class "Default")
      (node (ref "Module1") (pin "3") (pinfunction "Ethernet_Pair3_P_3") (pintype "power_in"))
      (node (ref "U1") (pin "1") (pinfunction "D1+_1") (pintype "passive"))
      (node (ref "U1") (pin "10") (pinfunction "NC_10_10") (pintype "passive"))
      (node (ref "U3") (pin "9") (pinfunction "TRD3+_9") (pintype "passive"))
    )
    (net (code "144") (name "/TV_OUT") (class "Default")
      (node (ref "J2") (pin "11") (pinfunction "11_11") (pintype "passive"))
      (node (ref "Module1") (pin "111") (pinfunction "VDAC_COMP_111") (pintype "power_in"))
    )
    (net (code "145") (name "/USB2_N") (class "Default")
      (node (ref "Module1") (pin "103") (pinfunction "USB2_N_103") (pintype "power_in"))
      (node (ref "U13") (pin "4") (pinfunction "D-_4") (pintype "bidirectional"))
    )
    (net (code "146") (name "/USB2_P") (class "Default")
      (node (ref "Module1") (pin "105") (pinfunction "USB2_P_105") (pintype "power_in"))
      (node (ref "U13") (pin "3") (pinfunction "D+_3") (pintype "bidirectional"))
    )
    (net (code "147") (name "/USBD_N") (class "Default")
      (node (ref "J11") (pin "2") (pinfunction "D-_2") (pintype "bidirectional"))
      (node (ref "U13") (pin "8") (pinfunction "HSD2-_8") (pintype "bidirectional"))
      (node (ref "U4") (pin "4") (pinfunction "D2+_4") (pintype "passive"))
      (node (ref "U4") (pin "7") (pinfunction "NC_7_7") (pintype "passive"))
    )
    (net (code "148") (name "/USBD_P") (class "Default")
      (node (ref "J11") (pin "3") (pinfunction "D+_3") (pintype "bidirectional"))
      (node (ref "U13") (pin "9") (pinfunction "HSD2+_9") (pintype "bidirectional"))
      (node (ref "U4") (pin "5") (pinfunction "D2-_5") (pintype "passive"))
      (node (ref "U4") (pin "6") (pinfunction "NC_6_6") (pintype "passive"))
    )
    (net (code "149") (name "/USBH_N") (class "Default")
      (node (ref "U13") (pin "6") (pinfunction "HSD1-_6") (pintype "bidirectional"))
      (node (ref "U6") (pin "30") (pinfunction "USBDM_UP_30") (pintype "bidirectional"))
    )
    (net (code "150") (name "/USBH_P") (class "Default")
      (node (ref "U13") (pin "7") (pinfunction "HSD1+_7") (pintype "bidirectional"))
      (node (ref "U6") (pin "31") (pinfunction "USBDP_UP_31") (pintype "bidirectional"))
    )
    (net (code "151") (name "/USBOTG") (class "Default")
      (node (ref "Module1") (pin "101") (pinfunction "USB_OTG_ID_101") (pintype "power_in"))
      (node (ref "R11") (pin "1") (pinfunction "1_1") (pintype "passive"))
      (node (ref "R8") (pin "2") (pinfunction "2_2") (pintype "passive"))
      (node (ref "U13") (pin "2") (pinfunction "SEL_2") (pintype "input"))
    )
    (net (code "152") (name "/WL_nDis") (class "Default")
      (node (ref "J3") (pin "1") (pinfunction "1_1") (pintype "passive"))
      (node (ref "Module1") (pin "89") (pinfunction "WL_nDisable_89") (pintype "power_in"))
    )
    (net (code "153") (name "/nEXTRST") (class "Default")
      (node (ref "Module1") (pin "100") (pinfunction "nEXTRST_100") (pintype "power_in"))
      (node (ref "U6") (pin "26") (pinfunction "RESET_N_26") (pintype "input"))
    )
    (net (code "154") (name "/nOSC1") (class "Default")
      (node (ref "U6") (pin "13") (pinfunction "OCS_N1_13") (pintype "input"))
      (node (ref "U6") (pin "17") (pinfunction "OCS_N2_17") (pintype "input"))
      (node (ref "U6") (pin "19") (pinfunction "OCS_N3_19") (pintype "input"))
      (node (ref "U6") (pin "21") (pinfunction "OCS_N4_21") (pintype "input"))
      (node (ref "U7") (pin "4") (pinfunction "nFault_4") (pintype "passive"))
    )
    (net (code "155") (name "/nPWR_LED") (class "Default")
      (node (ref "Module1") (pin "95") (pinfunction "nPI_LED_PWR_95") (pintype "power_in"))
      (node (ref "U5") (pin "2") (pinfunction "A_2") (pintype "passive"))
    )
    (net (code "156") (name "/nRPIBOOT") (class "Default")
      (node (ref "J2") (pin "2") (pinfunction "2_2") (pintype "passive"))
      (node (ref "Module1") (pin "93") (pinfunction "nRPIBOOT_93") (pintype "power_in"))
    )
    (net (code "157") (name "/nRTC_INT") (class "Default")
      (node (ref "C24") (pin "2") (pinfunction "2_2") (pintype "passive"))
      (node (ref "R19") (pin "1") (pinfunction "1_1") (pintype "passive"))
      (node (ref "U8") (pin "3") (pinfunction "~{INT}_3") (pintype "passive"))
    )
    (net (code "158") (name "GND") (class "Default")
      (node (ref "BT1") (pin "2") (pinfunction "-_2") (pintype "passive"))
      (node (ref "C1") (pin "2") (pinfunction "2_2") (pintype "passive"))
      (node (ref "C10") (pin "2") (pinfunction "2_2") (pintype "passive"))
      (node (ref "C11") (pin "2") (pinfunction "2_2") (pintype "passive"))
      (node (ref "C14") (pin "2") (pinfunction "2_2") (pintype "passive"))
      (node (ref "C15") (pin "2") (pinfunction "2_2") (pintype "passive"))
      (node (ref "C16") (pin "2") (pinfunction "2_2") (pintype "passive"))
      (node (ref "C17") (pin "2") (pinfunction "2_2") (pintype "passive"))
      (node (ref "C18") (pin "2") (pinfunction "2_2") (pintype "passive"))
      (node (ref "C19") (pin "2") (pinfunction "2_2") (pintype "passive"))
      (node (ref "C2") (pin "2") (pinfunction "2_2") (pintype "passive"))
      (node (ref "C20") (pin "2") (pinfunction "2_2") (pintype "passive"))
      (node (ref "C21") (pin "2") (pinfunction "2_2") (pintype "passive"))
      (node (ref "C22") (pin "2") (pinfunction "2_2") (pintype "passive"))
      (node (ref "C23") (pin "2") (pinfunction "2_2") (pintype "passive"))
      (node (ref "C25") (pin "2") (pinfunction "2_2") (pintype "passive"))
      (node (ref "C26") (pin "2") (pinfunction "2_2") (pintype "passive"))
      (node (ref "C27") (pin "2") (pinfunction "2_2") (pintype "passive"))
      (node (ref "C28") (pin "2") (pinfunction "2_2") (pintype "passive"))
      (node (ref "C3") (pin "2") (pinfunction "2_2") (pintype "passive"))
      (node (ref "C30") (pin "2") (pinfunction "2_2") (pintype "passive"))
      (node (ref "C31") (pin "2") (pinfunction "2_2") (pintype "passive"))
      (node (ref "C32") (pin "2") (pinfunction "2_2") (pintype "passive"))
      (node (ref "C33") (pin "2") (pinfunction "2_2") (pintype "passive"))
      (node (ref "C34") (pin "2") (pinfunction "2_2") (pintype "passive"))
      (node (ref "C35") (pin "2") (pinfunction "2_2") (pintype "passive"))
      (node (ref "C36") (pin "2") (pinfunction "2_2") (pintype "passive"))
      (node (ref "C37") (pin "2") (pinfunction "2_2") (pintype "passive"))
      (node (ref "C38") (pin "2") (pinfunction "2_2") (pintype "passive"))
      (node (ref "C39") (pin "2") (pinfunction "2_2") (pintype "passive"))
      (node (ref "C4") (pin "2") (pinfunction "2_2") (pintype "passive"))
      (node (ref "C41") (pin "2") (pinfunction "2_2") (pintype "passive"))
      (node (ref "C42") (pin "2") (pinfunction "2_2") (pintype "passive"))
      (node (ref "C43") (pin "2") (pinfunction "2_2") (pintype "passive"))
      (node (ref "C44") (pin "2") (pinfunction "2_2") (pintype "passive"))
      (node (ref "C45") (pin "2") (pinfunction "2_2") (pintype "passive"))
      (node (ref "C46") (pin "2") (pinfunction "2_2") (pintype "passive"))
      (node (ref "C47") (pin "2") (pinfunction "2_2") (pintype "passive"))
      (node (ref "C49") (pin "2") (pinfunction "2_2") (pintype "passive"))
      (node (ref "C5") (pin "2") (pinfunction "2_2") (pintype "passive"))
      (node (ref "C51") (pin "2") (pinfunction "2_2") (pintype "passive"))
      (node (ref "C52") (pin "2") (pinfunction "2_2") (pintype "passive"))
      (node (ref "C58") (pin "2") (pinfunction "2_2") (pintype "passive"))
      (node (ref "C59") (pin "2") (pinfunction "2_2") (pintype "passive"))
      (node (ref "C6") (pin "2") (pinfunction "2_2") (pintype "passive"))
      (node (ref "C60") (pin "2") (pinfunction "2_2") (pintype "passive"))
      (node (ref "C62") (pin "2") (pinfunction "2_2") (pintype "passive"))
      (node (ref "C63") (pin "2") (pinfunction "2_2") (pintype "passive"))
      (node (ref "C64") (pin "2") (pinfunction "2_2") (pintype "passive"))
      (node (ref "C7") (pin "2") (pinfunction "2_2") (pintype "passive"))
      (node (ref "C8") (pin "2") (pinfunction "2_2") (pintype "passive"))
      (node (ref "C9") (pin "2") (pinfunction "2_2") (pintype "passive"))
      (node (ref "J1") (pin "2") (pinfunction "2_2") (pintype "passive"))
      (node (ref "J11") (pin "5") (pinfunction "GND_5") (pintype "power_in"))
      (node (ref "J11") (pin "6") (pinfunction "Shield_6") (pintype "passive"))
      (node (ref "J12") (pin "A12") (pinfunction "GND_A12") (pintype "passive"))
      (node (ref "J12") (pin "A15") (pinfunction "GND_A15") (pintype "passive"))
      (node (ref "J12") (pin "A18") (pinfunction "GND_A18") (pintype "passive"))
      (node (ref "J12") (pin "A4") (pinfunction "GND_A4") (pintype "passive"))
      (node (ref "J12") (pin "B13") (pinfunction "GND_B13") (pintype "passive"))
      (node (ref "J12") (pin "B18") (pinfunction "GND_B18") (pintype "passive"))
      (node (ref "J12") (pin "B4") (pinfunction "GND_B4") (pintype "passive"))
      (node (ref "J12") (pin "B7") (pinfunction "GND_B7") (pintype "passive"))
      (node (ref "J13") (pin "4") (pinfunction "GND_1_4") (pintype "passive"))
      (node (ref "J13") (pin "8") (pinfunction "GND_2_8") (pintype "passive"))
      (node (ref "J13") (pin "MT1") (pinfunction "MT1_MT1") (pintype "passive"))
      (node (ref "J13") (pin "MT2") (pinfunction "MT2_MT2") (pintype "passive"))
      (node (ref "J13") (pin "MT3") (pinfunction "MT3_MT3") (pintype "passive"))
      (node (ref "J13") (pin "MT4") (pinfunction "MT4_MT4") (pintype "passive"))
      (node (ref "J15") (pin "1") (pinfunction "1_1") (pintype "passive"))
      (node (ref "J15") (pin "10") (pinfunction "10_10") (pintype "passive"))
      (node (ref "J15") (pin "13") (pinfunction "13_13") (pintype "passive"))
      (node (ref "J15") (pin "16") (pinfunction "16_16") (pintype "passive"))
      (node (ref "J15") (pin "19") (pinfunction "19_19") (pintype "passive"))
      (node (ref "J15") (pin "4") (pinfunction "4_4") (pintype "passive"))
      (node (ref "J15") (pin "7") (pinfunction "7_7") (pintype "passive"))
      (node (ref "J16") (pin "1") (pinfunction "1_1") (pintype "passive"))
      (node (ref "J16") (pin "10") (pinfunction "10_10") (pintype "passive"))
      (node (ref "J16") (pin "13") (pinfunction "13_13") (pintype "passive"))
      (node (ref "J16") (pin "16") (pinfunction "16_16") (pintype "passive"))
      (node (ref "J16") (pin "19") (pinfunction "19_19") (pintype "passive"))
      (node (ref "J16") (pin "4") (pinfunction "4_4") (pintype "passive"))
      (node (ref "J16") (pin "7") (pinfunction "7_7") (pintype "passive"))
      (node (ref "J17") (pin "1") (pinfunction "1_1") (pintype "passive"))
      (node (ref "J19") (pin "2") (pinfunction "2_2") (pintype "passive"))
      (node (ref "J19") (pin "3") (pinfunction "3_3") (pintype "passive"))
      (node (ref "J2") (pin "1") (pinfunction "1_1") (pintype "passive"))
      (node (ref "J2") (pin "10") (pinfunction "10_10") (pintype "passive"))
      (node (ref "J2") (pin "12") (pinfunction "12_12") (pintype "passive"))
      (node (ref "J2") (pin "3") (pinfunction "3_3") (pintype "passive"))
      (node (ref "J2") (pin "7") (pinfunction "7_7") (pintype "passive"))
      (node (ref "J20") (pin "2") (pinfunction "2_2") (pintype "passive"))
      (node (ref "J20") (pin "3") (pinfunction "3_3") (pintype "passive"))
      (node (ref "J3") (pin "2") (pinfunction "2_2") (pintype "passive"))
      (node (ref "J4") (pin "1") (pinfunction "1_1") (pintype "passive"))
      (node (ref "J4") (pin "10") (pinfunction "10_10") (pintype "passive"))
      (node (ref "J4") (pin "13") (pinfunction "13_13") (pintype "passive"))
      (node (ref "J4") (pin "16") (pinfunction "16_16") (pintype "passive"))
      (node (ref "J4") (pin "19") (pinfunction "19_19") (pintype "passive"))
      (node (ref "J4") (pin "4") (pinfunction "4_4") (pintype "passive"))
      (node (ref "J4") (pin "7") (pinfunction "7_7") (pintype "passive"))
      (node (ref "J5") (pin "1") (pinfunction "1_1") (pintype "passive"))
      (node (ref "J5") (pin "10") (pinfunction "10_10") (pintype "passive"))
      (node (ref "J5") (pin "13") (pinfunction "13_13") (pintype "passive"))
      (node (ref "J5") (pin "16") (pinfunction "16_16") (pintype "passive"))
      (node (ref "J5") (pin "19") (pinfunction "19_19") (pintype "passive"))
      (node (ref "J5") (pin "4") (pinfunction "4_4") (pintype "passive"))
      (node (ref "J5") (pin "7") (pinfunction "7_7") (pintype "passive"))
      (node (ref "J7") (pin "11") (pinfunction "SHIELD_11") (pintype "passive"))
      (node (ref "J7") (pin "6") (pinfunction "VSS_6") (pintype "power_in"))
      (node (ref "J8") (pin "14") (pinfunction "14_14") (pintype "passive"))
      (node (ref "J8") (pin "20") (pinfunction "20_20") (pintype "passive"))
      (node (ref "J8") (pin "25") (pinfunction "25_25") (pintype "passive"))
      (node (ref "J8") (pin "30") (pinfunction "30_30") (pintype "passive"))
      (node (ref "J8") (pin "34") (pinfunction "34_34") (pintype "passive"))
      (node (ref "J8") (pin "39") (pinfunction "39_39") (pintype "passive"))
      (node (ref "J8") (pin "6") (pinfunction "6_6") (pintype "passive"))
      (node (ref "J8") (pin "9") (pinfunction "9_9") (pintype "passive"))
      (node (ref "Module1") (pin "1") (pinfunction "GND_1") (pintype "power_in"))
      (node (ref "Module1") (pin "107") (pinfunction "GND_107") (pintype "power_in"))
      (node (ref "Module1") (pin "108") (pinfunction "GND_108") (pintype "power_in"))
      (node (ref "Module1") (pin "113") (pinfunction "GND_113") (pintype "power_in"))
      (node (ref "Module1") (pin "114") (pinfunction "GND_114") (pintype "power_in"))
      (node (ref "Module1") (pin "119") (pinfunction "GND_119") (pintype "power_in"))
      (node (ref "Module1") (pin "120") (pinfunction "GND_120") (pintype "power_in"))
      (node (ref "Module1") (pin "125") (pinfunction "GND_125") (pintype "power_in"))
      (node (ref "Module1") (pin "126") (pinfunction "GND_126") (pintype "power_in"))
      (node (ref "Module1") (pin "13") (pinfunction "GND_13") (pintype "power_in"))
      (node (ref "Module1") (pin "131") (pinfunction "GND_131") (pintype "power_in"))
      (node (ref "Module1") (pin "132") (pinfunction "GND_132") (pintype "power_in"))
      (node (ref "Module1") (pin "137") (pinfunction "GND_137") (pintype "power_in"))
      (node (ref "Module1") (pin "138") (pinfunction "GND_138") (pintype "power_in"))
      (node (ref "Module1") (pin "14") (pinfunction "GND_14") (pintype "power_in"))
      (node (ref "Module1") (pin "144") (pinfunction "GND_144") (pintype "power_in"))
      (node (ref "Module1") (pin "150") (pinfunction "GND_150") (pintype "power_in"))
      (node (ref "Module1") (pin "155") (pinfunction "GND_155") (pintype "power_in"))
      (node (ref "Module1") (pin "156") (pinfunction "GND_156") (pintype "power_in"))
      (node (ref "Module1") (pin "161") (pinfunction "GND_161") (pintype "power_in"))
      (node (ref "Module1") (pin "162") (pinfunction "GND_162") (pintype "power_in"))
      (node (ref "Module1") (pin "167") (pinfunction "GND_167") (pintype "power_in"))
      (node (ref "Module1") (pin "168") (pinfunction "GND_168") (pintype "power_in"))
      (node (ref "Module1") (pin "173") (pinfunction "GND_173") (pintype "power_in"))
      (node (ref "Module1") (pin "174") (pinfunction "GND_174") (pintype "power_in"))
      (node (ref "Module1") (pin "179") (pinfunction "GND_179") (pintype "power_in"))
      (node (ref "Module1") (pin "180") (pinfunction "GND_180") (pintype "power_in"))
      (node (ref "Module1") (pin "185") (pinfunction "GND_185") (pintype "power_in"))
      (node (ref "Module1") (pin "186") (pinfunction "GND_186") (pintype "power_in"))
      (node (ref "Module1") (pin "191") (pinfunction "GND_191") (pintype "power_in"))
      (node (ref "Module1") (pin "192") (pinfunction "GND_192") (pintype "power_in"))
      (node (ref "Module1") (pin "197") (pinfunction "GND_197") (pintype "power_in"))
      (node (ref "Module1") (pin "198") (pinfunction "GND_198") (pintype "power_in"))
      (node (ref "Module1") (pin "2") (pinfunction "GND_2") (pintype "power_in"))
      (node (ref "Module1") (pin "22") (pinfunction "GND_22") (pintype "power_in"))
      (node (ref "Module1") (pin "23") (pinfunction "GND_23") (pintype "power_in"))
      (node (ref "Module1") (pin "32") (pinfunction "GND_32") (pintype "power_in"))
      (node (ref "Module1") (pin "33") (pinfunction "GND_33") (pintype "power_in"))
      (node (ref "Module1") (pin "42") (pinfunction "GND_42") (pintype "power_in"))
      (node (ref "Module1") (pin "43") (pinfunction "GND_43") (pintype "power_in"))
      (node (ref "Module1") (pin "52") (pinfunction "GND_52") (pintype "power_in"))
      (node (ref "Module1") (pin "53") (pinfunction "GND_53") (pintype "power_in"))
      (node (ref "Module1") (pin "59") (pinfunction "GND_59") (pintype "power_in"))
      (node (ref "Module1") (pin "60") (pinfunction "GND_60") (pintype "power_in"))
      (node (ref "Module1") (pin "65") (pinfunction "GND_65") (pintype "power_in"))
      (node (ref "Module1") (pin "66") (pinfunction "GND_66") (pintype "power_in"))
      (node (ref "Module1") (pin "7") (pinfunction "GND_7") (pintype "power_in"))
      (node (ref "Module1") (pin "71") (pinfunction "GND_71") (pintype "power_in"))
      (node (ref "Module1") (pin "74") (pinfunction "GND_74") (pintype "power_in"))
      (node (ref "Module1") (pin "8") (pinfunction "GND_8") (pintype "power_in"))
      (node (ref "Module1") (pin "98") (pinfunction "GND_98") (pintype "power_in"))
      (node (ref "R11") (pin "2") (pinfunction "2_2") (pintype "passive"))
      (node (ref "R12") (pin "2") (pinfunction "2_2") (pintype "passive"))
      (node (ref "R13") (pin "2") (pinfunction "2_2") (pintype "passive"))
      (node (ref "R14") (pin "2") (pinfunction "2_2") (pintype "passive"))
      (node (ref "R15") (pin "1") (pinfunction "1_1") (pintype "passive"))
      (node (ref "R16") (pin "2") (pinfunction "2_2") (pintype "passive"))
      (node (ref "R26") (pin "2") (pinfunction "2_2") (pintype "passive"))
      (node (ref "R28") (pin "2") (pinfunction "2_2") (pintype "passive"))
      (node (ref "R30") (pin "2") (pinfunction "2_2") (pintype "passive"))
      (node (ref "R36") (pin "2") (pinfunction "2_2") (pintype "passive"))
      (node (ref "TP6") (pin "1") (pinfunction "1_1") (pintype "passive"))
      (node (ref "U1") (pin "3") (pinfunction "GND_3_3") (pintype "power_in"))
      (node (ref "U1") (pin "8") (pinfunction "GND_8_8") (pintype "power_in"))
      (node (ref "U11") (pin "4") (pinfunction "GND_4") (pintype "passive"))
      (node (ref "U13") (pin "10") (pinfunction "~{OE}_10") (pintype "input"))
      (node (ref "U13") (pin "5") (pinfunction "GND_5") (pintype "power_in"))
      (node (ref "U14") (pin "3") (pinfunction "GND_3") (pintype "passive"))
      (node (ref "U15") (pin "7") (pinfunction "GND_7") (pintype "passive"))
      (node (ref "U15") (pin "9") (pinfunction "EP_9") (pintype "passive"))
      (node (ref "U16") (pin "7") (pinfunction "GND_7") (pintype "passive"))
      (node (ref "U16") (pin "9") (pinfunction "EP_9") (pintype "passive"))
      (node (ref "U18") (pin "2") (pinfunction "GND_2") (pintype "passive"))
      (node (ref "U2") (pin "3") (pinfunction "GND_3_3") (pintype "power_in"))
      (node (ref "U2") (pin "8") (pinfunction "GND_8_8") (pintype "power_in"))
      (node (ref "U3") (pin "19") (pinfunction "SHIELD_19") (pintype "passive"))
      (node (ref "U3") (pin "20") (pinfunction "SHIELD_20") (pintype "passive"))
      (node (ref "U4") (pin "3") (pinfunction "GND_3_3") (pintype "power_in"))
      (node (ref "U4") (pin "8") (pinfunction "GND_8_8") (pintype "power_in"))
      (node (ref "U5") (pin "3") (pinfunction "GND_3") (pintype "passive"))
      (node (ref "U6") (pin "37") (pinfunction "VSS_37") (pintype "power_in"))
      (node (ref "U7") (pin "2") (pinfunction "GND_2") (pintype "passive"))
      (node (ref "U8") (pin "4") (pinfunction "VSS_4") (pintype "passive"))
      (node (ref "U9") (pin "3") (pinfunction "GND_3") (pintype "passive"))
    )
    (net (code "159") (name "Net-(BT1-+)") (class "Default")
      (node (ref "BT1") (pin "1") (pinfunction "+_1") (pintype "passive"))
      (node (ref "D3") (pin "1") (pinfunction "1_1") (pintype "passive"))
    )
    (net (code "160") (name "Net-(C1-Pad1)") (class "Default")
      (node (ref "C1") (pin "1") (pinfunction "1_1") (pintype "passive"))
      (node (ref "U3") (pin "4") (pinfunction "CT_4") (pintype "passive"))
      (node (ref "U3") (pin "5") (pinfunction "CT_5") (pintype "passive"))
    )
    (net (code "161") (name "Net-(C29-Pad1)") (class "Default")
      (node (ref "C29") (pin "1") (pinfunction "1_1") (pintype "passive"))
      (node (ref "R22") (pin "2") (pinfunction "2_2") (pintype "passive"))
    )
    (net (code "162") (name "Net-(C57-Pad1)") (class "Default")
      (node (ref "C57") (pin "1") (pinfunction "1_1") (pintype "passive"))
      (node (ref "R9") (pin "2") (pinfunction "2_2") (pintype "passive"))
    )
    (net (code "163") (name "Net-(C60-Pad1)") (class "Default")
      (node (ref "C60") (pin "1") (pinfunction "1_1") (pintype "passive"))
      (node (ref "R25") (pin "2") (pinfunction "2_2") (pintype "passive"))
    )
    (net (code "164") (name "Net-(C64-Pad1)") (class "Default")
      (node (ref "C64") (pin "1") (pinfunction "1_1") (pintype "passive"))
      (node (ref "R23") (pin "2") (pinfunction "2_2") (pintype "passive"))
    )
    (net (code "165") (name "Net-(D1-K)") (class "Default")
      (node (ref "D1") (pin "1") (pinfunction "K_1") (pintype "passive"))
      (node (ref "R10") (pin "1") (pinfunction "1_1") (pintype "passive"))
      (node (ref "TP5") (pin "1") (pinfunction "1_1") (pintype "passive"))
    )
    (net (code "166") (name "Net-(D2-K)") (class "Default")
      (node (ref "D2") (pin "1") (pinfunction "K_1") (pintype "passive"))
      (node (ref "R1") (pin "1") (pinfunction "1_1") (pintype "passive"))
      (node (ref "TP3") (pin "1") (pinfunction "1_1") (pintype "passive"))
    )
    (net (code "167") (name "Net-(D4-A)") (class "Default")
      (node (ref "C40") (pin "2") (pinfunction "2_2") (pintype "passive"))
      (node (ref "D4") (pin "2") (pinfunction "A_2") (pintype "passive"))
      (node (ref "Q1") (pin "4") (pinfunction "G_4") (pintype "passive"))
      (node (ref "R26") (pin "1") (pinfunction "1_1") (pintype "passive"))
    )
    (net (code "168") (name "Net-(J7-DETECT_A)") (class "Default")
      (node (ref "J7") (pin "10") (pinfunction "DETECT_A_10") (pintype "passive"))
      (node (ref "R17") (pin "2") (pinfunction "2_2") (pintype "passive"))
    )
    (net (code "169") (name "Net-(J7-DETECT_B)") (class "Default")
      (node (ref "J7") (pin "9") (pinfunction "DETECT_B_9") (pintype "power_in"))
      (node (ref "R18") (pin "2") (pinfunction "2_2") (pintype "passive"))
    )
    (net (code "170") (name "Net-(J11-VBUS)") (class "Default")
      (node (ref "J11") (pin "1") (pinfunction "VBUS_1") (pintype "power_in"))
      (node (ref "R8") (pin "1") (pinfunction "1_1") (pintype "passive"))
    )
    (net (code "171") (name "Net-(Module1A-Pi_nLED_Activity)") (class "Default")
      (node (ref "Module1") (pin "21") (pinfunction "Pi_nLED_Activity_21") (pintype "power_in"))
      (node (ref "R1") (pin "2") (pinfunction "2_2") (pintype "passive"))
    )
    (net (code "172") (name "Net-(Q1-D)") (class "Default")
      (node (ref "C36") (pin "1") (pinfunction "1_1") (pintype "passive"))
      (node (ref "J19") (pin "1") (pinfunction "1_1") (pintype "passive"))
      (node (ref "Q1") (pin "5") (pinfunction "D_5") (pintype "passive"))
    )
    (net (code "173") (name "Net-(U3-G_K)") (class "Default")
      (node (ref "R2") (pin "1") (pinfunction "1_1") (pintype "passive"))
      (node (ref "U3") (pin "16") (pinfunction "G_K_16") (pintype "passive"))
    )
    (net (code "174") (name "Net-(U3-Y_K)") (class "Default")
      (node (ref "R3") (pin "1") (pinfunction "1_1") (pintype "passive"))
      (node (ref "U3") (pin "18") (pinfunction "Y_K_18") (pintype "passive"))
    )
    (net (code "175") (name "Net-(U4-D1+)") (class "Default")
      (node (ref "U4") (pin "1") (pinfunction "D1+_1") (pintype "passive"))
      (node (ref "U4") (pin "10") (pinfunction "NC_10_10") (pintype "passive"))
    )
    (net (code "176") (name "Net-(U4-D1-)") (class "Default")
      (node (ref "U4") (pin "2") (pinfunction "D1-_2") (pintype "passive"))
      (node (ref "U4") (pin "9") (pinfunction "NC_9_9") (pintype "passive"))
    )
    (net (code "177") (name "Net-(U5-Y)") (class "Default")
      (node (ref "R10") (pin "2") (pinfunction "2_2") (pintype "passive"))
      (node (ref "U5") (pin "4") (pinfunction "Y_4") (pintype "passive"))
    )
    (net (code "178") (name "Net-(U6-HS_IND{slash}CFG_SEL1)") (class "Default")
      (node (ref "R16") (pin "1") (pinfunction "1_1") (pintype "passive"))
      (node (ref "U6") (pin "25") (pinfunction "HS_IND/CFG_SEL1_25") (pintype "input"))
    )
    (net (code "179") (name "Net-(U6-RBIAS)") (class "Default")
      (node (ref "R15") (pin "2") (pinfunction "2_2") (pintype "passive"))
      (node (ref "U6") (pin "35") (pinfunction "RBIAS_35") (pintype "bidirectional"))
    )
    (net (code "180") (name "Net-(U6-SCL{slash}CFG_SEL0{slash}SMBCLK)") (class "Default")
      (node (ref "R12") (pin "1") (pinfunction "1_1") (pintype "passive"))
      (node (ref "U6") (pin "24") (pinfunction "SCL/CFG_SEL0/SMBCLK_24") (pintype "input"))
    )
    (net (code "181") (name "Net-(U6-SDA{slash}SMBDATA{slash}NON_REM1)") (class "Default")
      (node (ref "R13") (pin "1") (pinfunction "1_1") (pintype "passive"))
      (node (ref "U6") (pin "22") (pinfunction "SDA/SMBDATA/NON_REM1_22") (pintype "bidirectional"))
    )
    (net (code "182") (name "Net-(U6-SUSP_IND{slash}LOCAL_PWR{slash}NON_REM0)") (class "Default")
      (node (ref "R14") (pin "1") (pinfunction "1_1") (pintype "passive"))
      (node (ref "U6") (pin "28") (pinfunction "SUSP_IND/LOCAL_PWR/NON_REM0_28") (pintype "bidirectional"))
    )
    (net (code "183") (name "Net-(U6-XTALIN{slash}CLKIN)") (class "Default")
      (node (ref "C8") (pin "1") (pinfunction "1_1") (pintype "passive"))
      (node (ref "U6") (pin "33") (pinfunction "XTALIN/CLKIN_33") (pintype "input"))
      (node (ref "Y1") (pin "1") (pinfunction "OSC1_1") (pintype "passive"))
    )
    (net (code "184") (name "Net-(U6-XTALOUT)") (class "Default")
      (node (ref "C9") (pin "1") (pinfunction "1_1") (pintype "passive"))
      (node (ref "U6") (pin "32") (pinfunction "XTALOUT_32") (pintype "output"))
      (node (ref "Y1") (pin "2") (pinfunction "OSC2_2") (pintype "passive"))
    )
    (net (code "185") (name "Net-(U7-ILIM)") (class "Default")
      (node (ref "R36") (pin "1") (pinfunction "1_1") (pintype "passive"))
      (node (ref "U7") (pin "5") (pinfunction "ILIM_5") (pintype "passive"))
    )
    (net (code "186") (name "Net-(U8-OSCI)") (class "Default")
      (node (ref "U8") (pin "1") (pinfunction "OSCI_1") (pintype "passive"))
      (node (ref "Y2") (pin "2") (pinfunction "OSC2_2") (pintype "passive"))
    )
    (net (code "187") (name "Net-(U8-OSCO)") (class "Default")
      (node (ref "U8") (pin "2") (pinfunction "OSCO_2") (pintype "passive"))
      (node (ref "Y2") (pin "1") (pinfunction "OSC1_1") (pintype "passive"))
    )
    (net (code "188") (name "Net-(U8-VDD)") (class "Default")
      (node (ref "C46") (pin "1") (pinfunction "1_1") (pintype "passive"))
      (node (ref "D3") (pin "3") (pinfunction "3_3") (pintype "passive"))
      (node (ref "U8") (pin "8") (pinfunction "VDD_8") (pintype "passive"))
    )
    (net (code "189") (name "Net-(U9-Y)") (class "Default")
      (node (ref "J2") (pin "13") (pinfunction "13_13") (pintype "passive"))
      (node (ref "U9") (pin "4") (pinfunction "Y_4") (pintype "passive"))
    )
    (net (code "190") (name "Net-(U11-PWM)") (class "Default")
      (node (ref "J17") (pin "4") (pinfunction "4_4") (pintype "passive"))
      (node (ref "U11") (pin "5") (pinfunction "PWM_5") (pintype "passive"))
    )
    (net (code "191") (name "Net-(U11-TACH)") (class "Default")
      (node (ref "J17") (pin "3") (pinfunction "3_3") (pintype "passive"))
      (node (ref "R21") (pin "1") (pinfunction "1_1") (pintype "passive"))
      (node (ref "U11") (pin "6") (pinfunction "TACH_6") (pintype "passive"))
    )
    (net (code "192") (name "Net-(U14-A)") (class "Default")
      (node (ref "C24") (pin "1") (pinfunction "1_1") (pintype "passive"))
      (node (ref "R20") (pin "1") (pinfunction "1_1") (pintype "passive"))
      (node (ref "U14") (pin "2") (pinfunction "A_2") (pintype "passive"))
    )
    (net (code "193") (name "Net-(U15-BST)") (class "Default")
      (node (ref "C29") (pin "2") (pinfunction "2_2") (pintype "passive"))
      (node (ref "U15") (pin "1") (pinfunction "BST_1") (pintype "passive"))
    )
    (net (code "194") (name "Net-(U15-COMP)") (class "Default")
      (node (ref "C63") (pin "1") (pinfunction "1_1") (pintype "passive"))
      (node (ref "R23") (pin "1") (pinfunction "1_1") (pintype "passive"))
      (node (ref "U15") (pin "6") (pinfunction "COMP_6") (pintype "passive"))
    )
    (net (code "195") (name "Net-(U15-FB)") (class "Default")
      (node (ref "C65") (pin "2") (pinfunction "2_2") (pintype "passive"))
      (node (ref "R24") (pin "2") (pinfunction "2_2") (pintype "passive"))
      (node (ref "R30") (pin "1") (pinfunction "1_1") (pintype "passive"))
      (node (ref "U15") (pin "5") (pinfunction "FB_5") (pintype "passive"))
    )
    (net (code "196") (name "Net-(U15-SS)") (class "Default")
      (node (ref "C62") (pin "1") (pinfunction "1_1") (pintype "passive"))
      (node (ref "U15") (pin "4") (pinfunction "SS_4") (pintype "passive"))
    )
    (net (code "197") (name "Net-(U15-SW)") (class "Default")
      (node (ref "L3") (pin "1") (pinfunction "1_1") (pintype "passive"))
      (node (ref "R22") (pin "1") (pinfunction "1_1") (pintype "passive"))
      (node (ref "U15") (pin "8") (pinfunction "SW_8") (pintype "passive"))
    )
    (net (code "198") (name "Net-(U16-BST)") (class "Default")
      (node (ref "C57") (pin "2") (pinfunction "2_2") (pintype "passive"))
      (node (ref "U16") (pin "1") (pinfunction "BST_1") (pintype "passive"))
    )
    (net (code "199") (name "Net-(U16-COMP)") (class "Default")
      (node (ref "C59") (pin "1") (pinfunction "1_1") (pintype "passive"))
      (node (ref "R25") (pin "1") (pinfunction "1_1") (pintype "passive"))
      (node (ref "U16") (pin "6") (pinfunction "COMP_6") (pintype "passive"))
    )
    (net (code "200") (name "Net-(U16-FB)") (class "Default")
      (node (ref "C61") (pin "2") (pinfunction "2_2") (pintype "passive"))
      (node (ref "R27") (pin "2") (pinfunction "2_2") (pintype "passive"))
      (node (ref "R28") (pin "1") (pinfunction "1_1") (pintype "passive"))
      (node (ref "U16") (pin "5") (pinfunction "FB_5") (pintype "passive"))
    )
    (net (code "201") (name "Net-(U16-SS)") (class "Default")
      (node (ref "C58") (pin "1") (pinfunction "1_1") (pintype "passive"))
      (node (ref "U16") (pin "4") (pinfunction "SS_4") (pintype "passive"))
    )
    (net (code "202") (name "Net-(U16-SW)") (class "Default")
      (node (ref "L5") (pin "1") (pinfunction "1_1") (pintype "passive"))
      (node (ref "R9") (pin "1") (pinfunction "1_1") (pintype "passive"))
      (node (ref "U16") (pin "8") (pinfunction "SW_8") (pintype "passive"))
    )
    (net (code "203") (name "VBUS") (class "Default")
      (node (ref "C16") (pin "1") (pinfunction "1_1") (pintype "passive"))
      (node (ref "C17") (pin "1") (pinfunction "1_1") (pintype "passive"))
      (node (ref "C19") (pin "1") (pinfunction "1_1") (pintype "passive"))
      (node (ref "C20") (pin "1") (pinfunction "1_1") (pintype "passive"))
      (node (ref "C21") (pin "1") (pinfunction "1_1") (pintype "passive"))
      (node (ref "J13") (pin "1") (pinfunction "VBUS_1_1") (pintype "passive"))
      (node (ref "J13") (pin "5") (pinfunction "VBUS_2_5") (pintype "passive"))
      (node (ref "U7") (pin "6") (pinfunction "OUT_6") (pintype "passive"))
    )
    (net (code "204") (name "unconnected-(H1-PadUn1)") (class "Default")
      (node (ref "H1") (pin "Un1") (pinfunction "Un1_Un1") (pintype "passive"))
    )
    (net (code "205") (name "unconnected-(H2-PadUn1)") (class "Default")
      (node (ref "H2") (pin "Un1") (pinfunction "Un1_Un1") (pintype "passive"))
    )
    (net (code "206") (name "unconnected-(H3-PadUn1)") (class "Default")
      (node (ref "H3") (pin "Un1") (pinfunction "Un1_Un1") (pintype "passive"))
    )
    (net (code "207") (name "unconnected-(H4-PadUn1)") (class "Default")
      (node (ref "H4") (pin "Un1") (pinfunction "Un1_Un1") (pintype "passive"))
    )
    (net (code "208") (name "unconnected-(H5-PadUn1)") (class "Default")
      (node (ref "H5") (pin "Un1") (pinfunction "Un1_Un1") (pintype "passive"))
    )
    (net (code "209") (name "unconnected-(H6-PadUn1)") (class "Default")
      (node (ref "H6") (pin "Un1") (pinfunction "Un1_Un1") (pintype "passive"))
    )
    (net (code "210") (name "unconnected-(H7-PadUn1)") (class "Default")
      (node (ref "H7") (pin "Un1") (pinfunction "Un1_Un1") (pintype "passive"))
    )
    (net (code "211") (name "unconnected-(H8-PadUn1)") (class "Default")
      (node (ref "H8") (pin "Un1") (pinfunction "Un1_Un1") (pintype "passive"))
    )
    (net (code "212") (name "unconnected-(J4-Pad11)") (class "Default")
      (node (ref "J4") (pin "11") (pinfunction "11_11") (pintype "passive"))
    )
    (net (code "213") (name "unconnected-(J4-Pad12)") (class "Default")
      (node (ref "J4") (pin "12") (pinfunction "12_12") (pintype "passive"))
    )
    (net (code "214") (name "unconnected-(J4-Pad14)") (class "Default")
      (node (ref "J4") (pin "14") (pinfunction "14_14") (pintype "passive"))
    )
    (net (code "215") (name "unconnected-(J4-Pad15)") (class "Default")
      (node (ref "J4") (pin "15") (pinfunction "15_15") (pintype "passive"))
    )
    (net (code "216") (name "unconnected-(J4-Pad18)") (class "Default")
      (node (ref "J4") (pin "18") (pinfunction "18_18") (pintype "passive"))
    )
    (net (code "217") (name "unconnected-(J5-Pad18)") (class "Default")
      (node (ref "J5") (pin "18") (pinfunction "18_18") (pintype "passive"))
    )
    (net (code "218") (name "unconnected-(J11-ID-Pad4)") (class "Default")
      (node (ref "J11") (pin "4") (pinfunction "ID_4") (pintype "passive"))
    )
    (net (code "219") (name "unconnected-(J12-GND-PadB16)") (class "Default")
      (node (ref "J12") (pin "B16") (pinfunction "GND_B16") (pintype "passive"))
    )
    (net (code "220") (name "unconnected-(J12-SMCLK-PadB5)") (class "Default")
      (node (ref "J12") (pin "B5") (pinfunction "SMCLK_B5") (pintype "passive"))
    )
    (net (code "221") (name "unconnected-(J12-SMDAT-PadB6)") (class "Default")
      (node (ref "J12") (pin "B6") (pinfunction "SMDAT_B6") (pintype "passive"))
    )
    (net (code "222") (name "unconnected-(J12-TDO-PadA7)") (class "Default")
      (node (ref "J12") (pin "A7") (pinfunction "TDO_A7") (pintype "passive"))
    )
    (net (code "223") (name "unconnected-(J12-nPRSNT1-PadA1)") (class "Default")
      (node (ref "J12") (pin "A1") (pinfunction "nPRSNT1_A1") (pintype "passive"))
    )
    (net (code "224") (name "unconnected-(J12-nPRSNT2-PadB17)") (class "Default")
      (node (ref "J12") (pin "B17") (pinfunction "nPRSNT2_B17") (pintype "passive"))
    )
    (net (code "225") (name "unconnected-(J12-nWAKE-PadB11)") (class "Default")
      (node (ref "J12") (pin "B11") (pinfunction "nWAKE_B11") (pintype "passive"))
    )
    (net (code "226") (name "unconnected-(J15-Pad11)") (class "Default")
      (node (ref "J15") (pin "11") (pinfunction "11_11") (pintype "passive"))
    )
    (net (code "227") (name "unconnected-(J15-Pad12)") (class "Default")
      (node (ref "J15") (pin "12") (pinfunction "12_12") (pintype "passive"))
    )
    (net (code "228") (name "unconnected-(J15-Pad14)") (class "Default")
      (node (ref "J15") (pin "14") (pinfunction "14_14") (pintype "passive"))
    )
    (net (code "229") (name "unconnected-(J15-Pad15)") (class "Default")
      (node (ref "J15") (pin "15") (pinfunction "15_15") (pintype "passive"))
    )
    (net (code "230") (name "unconnected-(J15-Pad17)") (class "Default")
      (node (ref "J15") (pin "17") (pinfunction "17_17") (pintype "passive"))
    )
    (net (code "231") (name "unconnected-(J15-Pad18)") (class "Default")
      (node (ref "J15") (pin "18") (pinfunction "18_18") (pintype "passive"))
    )
    (net (code "232") (name "unconnected-(J16-Pad17)") (class "Default")
      (node (ref "J16") (pin "17") (pinfunction "17_17") (pintype "passive"))
    )
    (net (code "233") (name "unconnected-(J16-Pad18)") (class "Default")
      (node (ref "J16") (pin "18") (pinfunction "18_18") (pintype "passive"))
    )
    (net (code "234") (name "unconnected-(Module1A-Ethernet_nLED1(3.3V)-Pad19)") (class "Default")
      (node (ref "Module1") (pin "19") (pinfunction "Ethernet_nLED1(3.3V)_19") (pintype "power_in"))
    )
    (net (code "235") (name "unconnected-(Module1A-SD_DATA4-Pad68)") (class "Default")
      (node (ref "Module1") (pin "68") (pinfunction "SD_DATA4_68") (pintype "power_in"))
    )
    (net (code "236") (name "unconnected-(Module1A-SD_DATA5-Pad64)") (class "Default")
      (node (ref "Module1") (pin "64") (pinfunction "SD_DATA5_64") (pintype "power_in"))
    )
    (net (code "237") (name "unconnected-(Module1A-SD_DATA6-Pad72)") (class "Default")
      (node (ref "Module1") (pin "72") (pinfunction "SD_DATA6_72") (pintype "power_in"))
    )
    (net (code "238") (name "unconnected-(Module1A-SD_DATA7-Pad70)") (class "Default")
      (node (ref "Module1") (pin "70") (pinfunction "SD_DATA7_70") (pintype "power_in"))
    )
    (net (code "239") (name "unconnected-(Module1A-SD_VDD_Override-Pad73)") (class "Default")
      (node (ref "Module1") (pin "73") (pinfunction "SD_VDD_Override_73") (pintype "power_in"))
    )
    (net (code "240") (name "unconnected-(Module1B-Reserved-Pad104)") (class "Default")
      (node (ref "Module1") (pin "104") (pinfunction "Reserved_104") (pintype "power_in"))
    )
    (net (code "241") (name "unconnected-(Module1B-Reserved-Pad106)") (class "Default")
      (node (ref "Module1") (pin "106") (pinfunction "Reserved_106") (pintype "power_in"))
    )
    (net (code "242") (name "unconnected-(U6-CRFILT-Pad14)") (class "Default")
      (node (ref "U6") (pin "14") (pinfunction "CRFILT_14") (pintype "passive"))
    )
    (net (code "243") (name "unconnected-(U6-PLLFILT-Pad34)") (class "Default")
      (node (ref "U6") (pin "34") (pinfunction "PLLFILT_34") (pintype "passive"))
    )
    (net (code "244") (name "unconnected-(U6-PRTPWR2{slash}BC_EN2-Pad16)") (class "Default")
      (node (ref "U6") (pin "16") (pinfunction "PRTPWR2/BC_EN2_16") (pintype "input"))
    )
    (net (code "245") (name "unconnected-(U6-PRTPWR3{slash}BC_EN3-Pad18)") (class "Default")
      (node (ref "U6") (pin "18") (pinfunction "PRTPWR3/BC_EN3_18") (pintype "input"))
    )
    (net (code "246") (name "unconnected-(U6-PRTPWR4{slash}BC_EN4-Pad20)") (class "Default")
      (node (ref "U6") (pin "20") (pinfunction "PRTPWR4/BC_EN4_20") (pintype "input"))
    )
    (net (code "247") (name "unconnected-(U6-TEST-Pad11)") (class "Default")
      (node (ref "U6") (pin "11") (pinfunction "TEST_11") (pintype "input"))
    )
    (net (code "248") (name "unconnected-(U8-CLKO-Pad7)") (class "Default")
      (node (ref "U8") (pin "7") (pinfunction "CLKO_7") (pintype "passive"))
    )
    (net (code "249") (name "unconnected-(U11-CLK-Pad7)") (class "Default")
      (node (ref "U11") (pin "7") (pinfunction "CLK_7") (pintype "passive"))
    )
    (net (code "250") (name "unconnected-(U11-nALERT-Pad8)") (class "Default")
      (node (ref "U11") (pin "8") (pinfunction "nALERT_8") (pintype "passive"))
    )
    (net (code "251") (name "unconnected-(U18-nFLG-Pad3)") (class "Default")
      (node (ref "U18") (pin "3") (pinfunction "nFLG_3") (pintype "passive"))
    )
  )
)
